# Pack_Supervisor_97x127mm_Rev_B.net
KiCad netlist of a schematic drawn in EAGLE
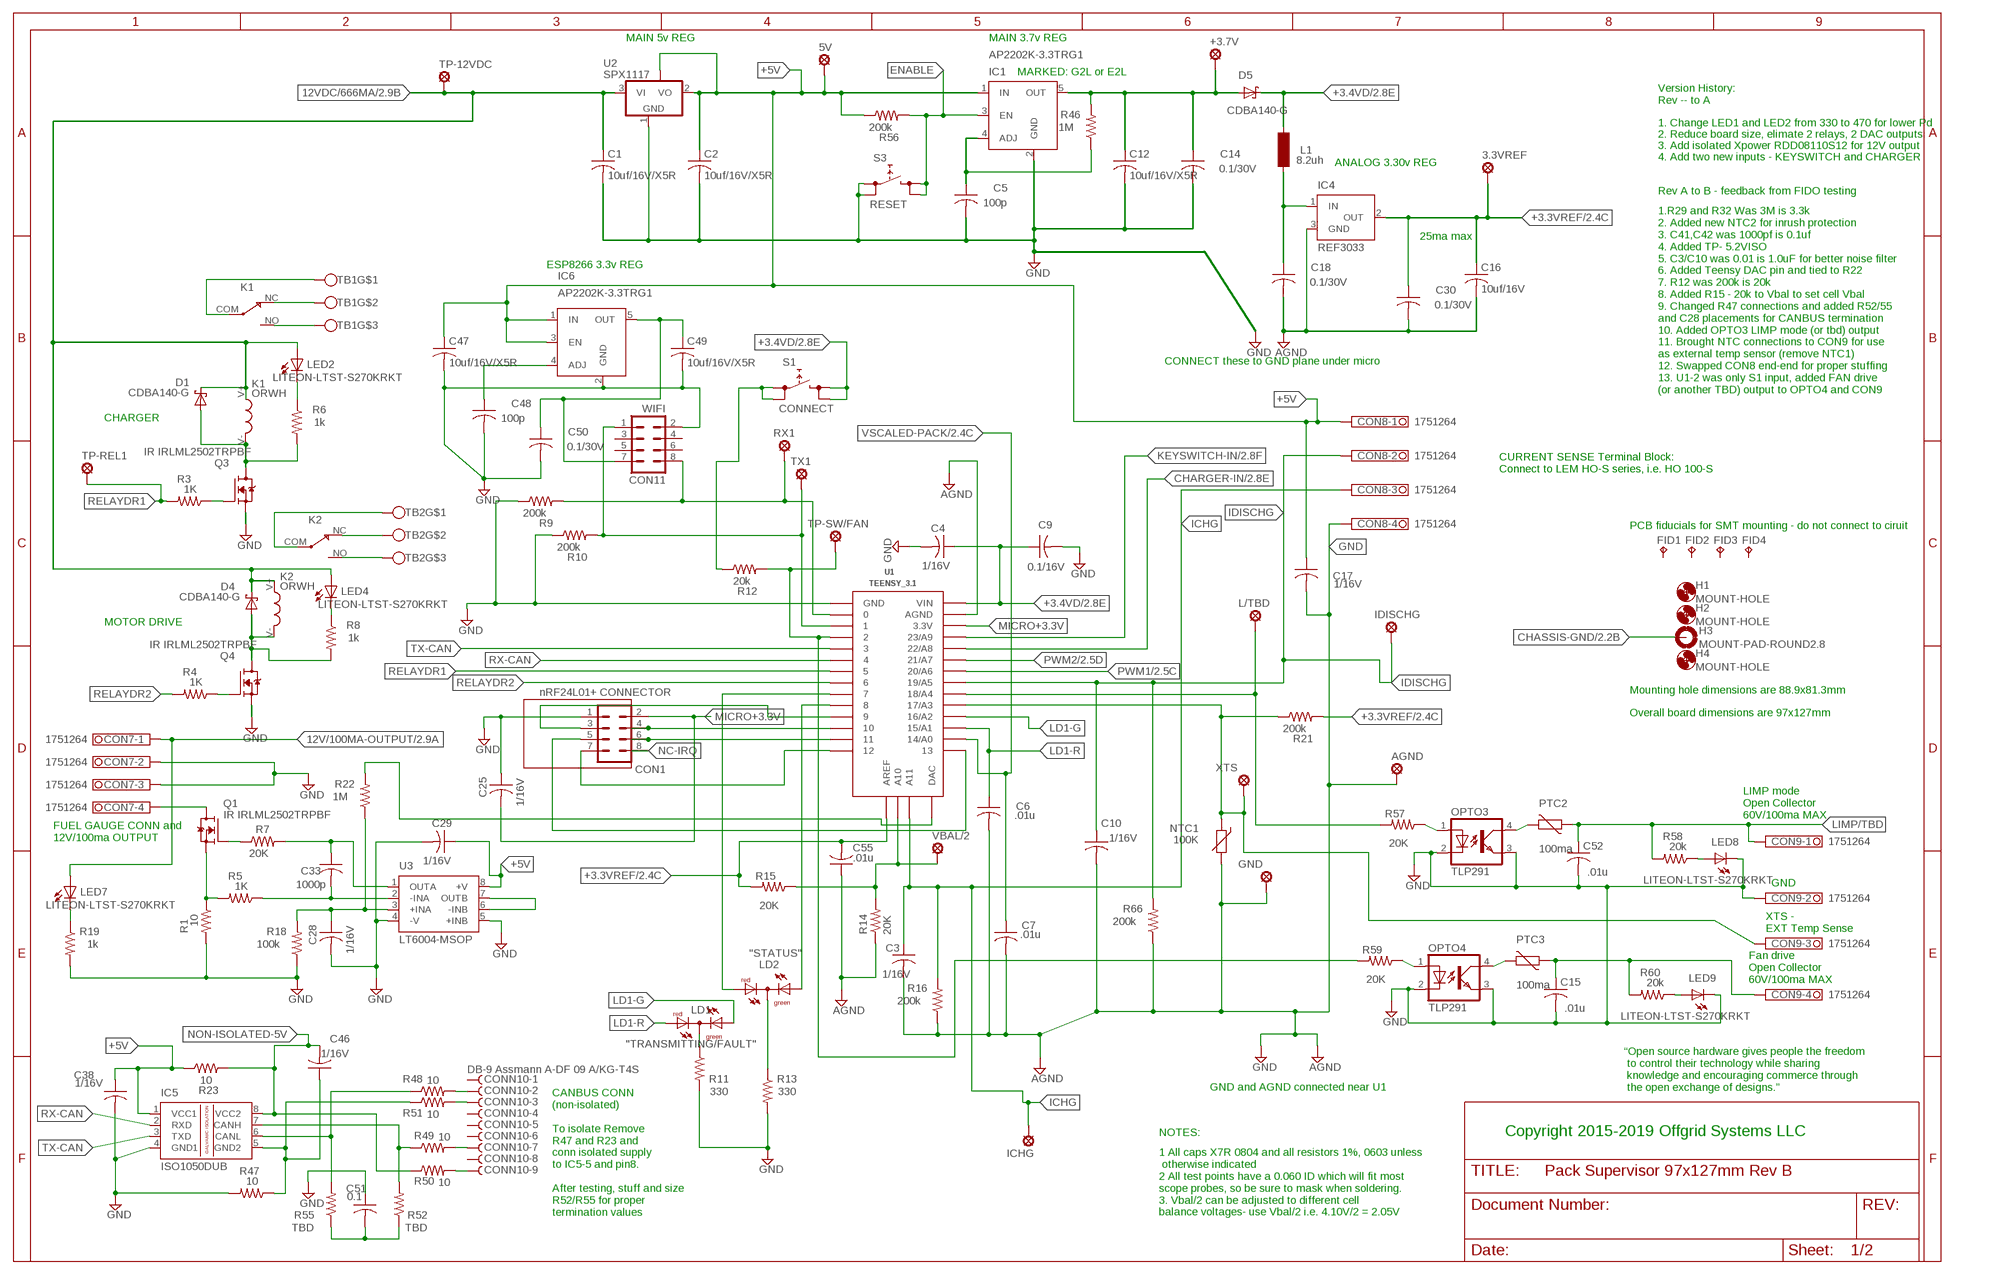
[diagram p0: schematic, sheet 1]
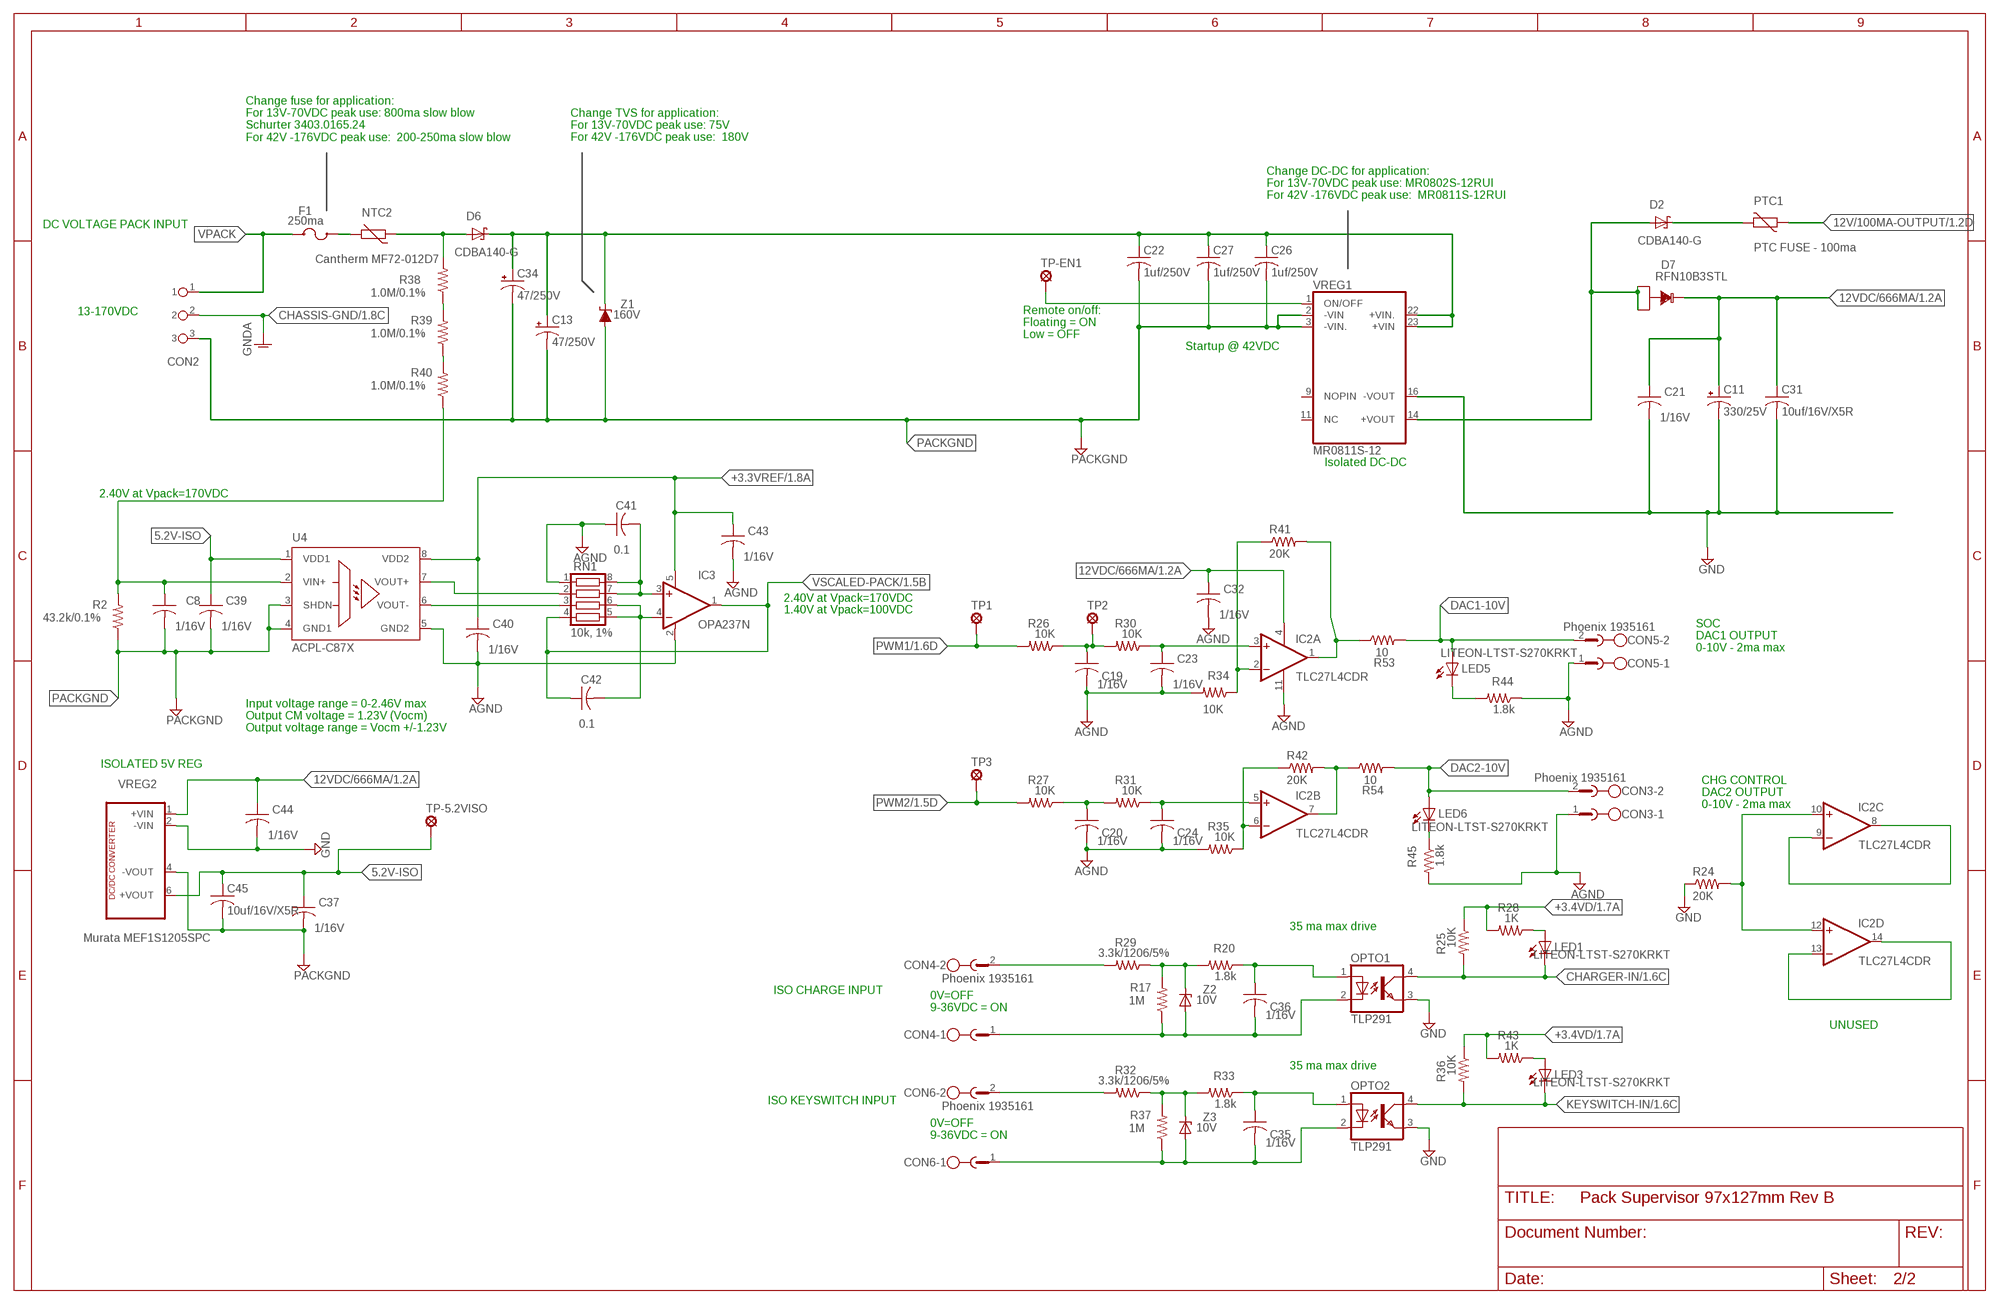
[diagram p1: schematic, sheet 2]

(export (version "E")
  (design (tool "Eeschema 10.0.6"))
  (components
    (comp (ref "+3.7V")
      (value "LSP10")
      (footprint "eagle-import:LSP10")
      (libsource (lib "eagle-import") (part "LSP10"))
    )
    (comp (ref "3.3VREF")
      (value "LSP10")
      (footprint "eagle-import:LSP10")
      (libsource (lib "eagle-import") (part "LSP10"))
    )
    (comp (ref "5V")
      (value "LSP10")
      (footprint "eagle-import:LSP10")
      (libsource (lib "eagle-import") (part "LSP10"))
    )
    (comp (ref "AGND")
      (value "LSP10")
      (footprint "eagle-import:LSP10")
      (libsource (lib "eagle-import") (part "LSP10"))
    )
    (comp (ref "C1")
      (value "10uf/16V/X5R")
      (footprint "eagle-import:C0805K")
      (fields (field (name "MPN") "Murata GRM21BR61C106ME15L"))
      (libsource (lib "eagle-import") (part "C-USC0805K"))
    )
    (comp (ref "C2")
      (value "10uf/16V/X5R")
      (footprint "eagle-import:C0805K")
      (fields (field (name "MPN") "Murata GRM21BR61C106ME15L"))
      (libsource (lib "eagle-import") (part "C-USC0805K"))
    )
    (comp (ref "C3")
      (value "1/16V")
      (footprint "eagle-import:TIMS_INDUCTOR_C0805")
      (fields (field (name "MPN") "Kemet C0805C103K5RACTU"))
      (libsource (lib "eagle-import") (part "TIMS_INDUCTOR_C-USC0805"))
    )
    (comp (ref "C4")
      (value "1/16V")
      (footprint "eagle-import:TIMS_INDUCTOR_C0805")
      (fields (field (name "MPN") "Kemet C0805C105K4RACTU"))
      (libsource (lib "eagle-import") (part "TIMS_INDUCTOR_C-USC0805"))
    )
    (comp (ref "C5")
      (value "100p")
      (footprint "eagle-import:TIMS_INDUCTOR_C0805")
      (fields (field (name "MPN") "Kemet C0805C104K5RACTU"))
      (libsource (lib "eagle-import") (part "TIMS_INDUCTOR_C-USC0805"))
    )
    (comp (ref "C6")
      (value ".01u")
      (footprint "eagle-import:TIMS_INDUCTOR_C0805")
      (fields (field (name "MPN") "Kemet C0805C103K5RACTU"))
      (libsource (lib "eagle-import") (part "TIMS_INDUCTOR_C-USC0805"))
    )
    (comp (ref "C7")
      (value ".01u")
      (footprint "eagle-import:TIMS_INDUCTOR_C0805")
      (fields (field (name "MPN") "Kemet C0805C103K5RACTU"))
      (libsource (lib "eagle-import") (part "TIMS_INDUCTOR_C-USC0805"))
    )
    (comp (ref "C9")
      (value "0.1/16V")
      (footprint "eagle-import:TIMS_INDUCTOR_C0805")
      (fields (field (name "MPN") "Kemet C0805C104K5RACTU"))
      (libsource (lib "eagle-import") (part "TIMS_INDUCTOR_C-USC0805"))
    )
    (comp (ref "C10")
      (value "1/16V")
      (footprint "eagle-import:TIMS_INDUCTOR_C0805")
      (fields (field (name "MPN") "Kemet C0805C103K5RACTU"))
      (libsource (lib "eagle-import") (part "TIMS_INDUCTOR_C-USC0805"))
    )
    (comp (ref "C12")
      (value "10uf/16V/X5R")
      (footprint "eagle-import:C0805K")
      (fields (field (name "MPN") "Murata GRM21BR61C106ME15L"))
      (libsource (lib "eagle-import") (part "C-USC0805K"))
    )
    (comp (ref "C14")
      (value "0.1/30V")
      (footprint "eagle-import:TIMS_INDUCTOR_C0805")
      (fields (field (name "MPN") "Kemet C0805C104K5RACTU"))
      (libsource (lib "eagle-import") (part "TIMS_INDUCTOR_C-USC0805"))
    )
    (comp (ref "C15")
      (value ".01u")
      (footprint "eagle-import:TIMS_INDUCTOR_C0805")
      (fields (field (name "MPN") "Kemet C0805C103K5RACTU"))
      (libsource (lib "eagle-import") (part "TIMS_INDUCTOR_C-USC0805"))
    )
    (comp (ref "C16")
      (value "10uf/16V")
      (footprint "eagle-import:C0805K")
      (fields (field (name "MPN") "Murata GRM21BR61A476ME15L"))
      (libsource (lib "eagle-import") (part "C-USC0805K"))
    )
    (comp (ref "C17")
      (value "1/16V")
      (footprint "eagle-import:TIMS_INDUCTOR_C0805")
      (fields (field (name "MPN") "Kemet C0805C105K4RACTU"))
      (libsource (lib "eagle-import") (part "TIMS_INDUCTOR_C-USC0805"))
    )
    (comp (ref "C18")
      (value "0.1/30V")
      (footprint "eagle-import:TIMS_INDUCTOR_C0805")
      (fields (field (name "MPN") "Kemet C0805C104K5RACTU"))
      (libsource (lib "eagle-import") (part "TIMS_INDUCTOR_C-USC0805"))
    )
    (comp (ref "C25")
      (value "1/16V")
      (footprint "eagle-import:TIMS_INDUCTOR_C0805")
      (fields (field (name "MPN") "Kemet C0805C105K4RACTU"))
      (libsource (lib "eagle-import") (part "TIMS_INDUCTOR_C-USC0805"))
    )
    (comp (ref "C28")
      (value "1/16V")
      (footprint "eagle-import:TIMS_INDUCTOR_C0805")
      (fields (field (name "MPN") "Kemet C0805C105K4RACTU"))
      (libsource (lib "eagle-import") (part "TIMS_INDUCTOR_C-USC0805"))
    )
    (comp (ref "C29")
      (value "1/16V")
      (footprint "eagle-import:TIMS_INDUCTOR_C0805")
      (fields (field (name "MPN") "Kemet C0805C105K4RACTU"))
      (libsource (lib "eagle-import") (part "TIMS_INDUCTOR_C-USC0805"))
    )
    (comp (ref "C30")
      (value "0.1/30V")
      (footprint "eagle-import:TIMS_INDUCTOR_C0805")
      (fields (field (name "MPN") "Kemet C0805C104K5RACTU"))
      (libsource (lib "eagle-import") (part "TIMS_INDUCTOR_C-USC0805"))
    )
    (comp (ref "C33")
      (value "1000p")
      (footprint "eagle-import:TIMS_INDUCTOR_C0805")
      (fields (field (name "MPN") "Kemet C0805C105K4RACTU"))
      (libsource (lib "eagle-import") (part "TIMS_INDUCTOR_C-USC0805"))
    )
    (comp (ref "C38")
      (value "1/16V")
      (footprint "eagle-import:TIMS_INDUCTOR_C0805")
      (fields (field (name "MPN") "Kemet C0805C105K4RACTU"))
      (libsource (lib "eagle-import") (part "TIMS_INDUCTOR_C-USC0805"))
    )
    (comp (ref "C46")
      (value "1/16V")
      (footprint "eagle-import:TIMS_INDUCTOR_C0805")
      (fields (field (name "MPN") "Kemet C0805C105K4RACTU"))
      (libsource (lib "eagle-import") (part "TIMS_INDUCTOR_C-USC0805"))
    )
    (comp (ref "C47")
      (value "10uf/16V/X5R")
      (footprint "eagle-import:C0805K")
      (fields (field (name "MPN") "Murata GRM21BR61C106ME15L"))
      (libsource (lib "eagle-import") (part "C-USC0805K"))
    )
    (comp (ref "C48")
      (value "100p")
      (footprint "eagle-import:TIMS_INDUCTOR_C0805")
      (fields (field (name "MPN") "Kemet C0805C104K5RACTU"))
      (libsource (lib "eagle-import") (part "TIMS_INDUCTOR_C-USC0805"))
    )
    (comp (ref "C49")
      (value "10uf/16V/X5R")
      (footprint "eagle-import:C0805K")
      (fields (field (name "MPN") "Murata GRM21BR61C106ME15L"))
      (libsource (lib "eagle-import") (part "C-USC0805K"))
    )
    (comp (ref "C50")
      (value "0.1/30V")
      (footprint "eagle-import:TIMS_INDUCTOR_C0805")
      (fields (field (name "MPN") "Kemet C0805C104K5RACTU"))
      (libsource (lib "eagle-import") (part "TIMS_INDUCTOR_C-USC0805"))
    )
    (comp (ref "C51")
      (value "0.1")
      (footprint "eagle-import:TIMS_INDUCTOR_C0805")
      (fields (field (name "MPN") "Kemet C0805C105K4RACTU"))
      (libsource (lib "eagle-import") (part "TIMS_INDUCTOR_C-USC0805"))
    )
    (comp (ref "C52")
      (value ".01u")
      (footprint "eagle-import:TIMS_INDUCTOR_C0805")
      (fields (field (name "MPN") "Kemet C0805C103K5RACTU"))
      (libsource (lib "eagle-import") (part "TIMS_INDUCTOR_C-USC0805"))
    )
    (comp (ref "C55")
      (value ".01u")
      (footprint "eagle-import:C0805")
      (fields (field (name "MPN") "Welwyn PCF0603R-3K01BT1"))
      (libsource (lib "eagle-import") (part "C-USC0805"))
    )
    (comp (ref "CON1")
      (value "nRF24L01+ CONNECTOR")
      (footprint "eagle-import:NRF24L01")
      (libsource (lib "eagle-import") (part "NRF24L01"))
    )
    (comp (ref "CON7")
      (value "1751264")
      (footprint "eagle-import:1751264")
      (libsource (lib "eagle-import") (part "1751264"))
    )
    (comp (ref "CON8")
      (value "1751264")
      (footprint "eagle-import:1751264")
      (libsource (lib "eagle-import") (part "1751264"))
    )
    (comp (ref "CON9")
      (value "1751264")
      (footprint "eagle-import:1751264")
      (libsource (lib "eagle-import") (part "1751264"))
    )
    (comp (ref "CON11")
      (value "WIFI")
      (footprint "eagle-import:MA04-2")
      (fields (field (name "MPN") "Sullins PPPC042LFBN-RC"))
      (libsource (lib "eagle-import") (part "MA04-2"))
    )
    (comp (ref "CONN10")
      (value "DB-9 Assmann A-DF 09 A/KG-T4S")
      (footprint "eagle-import:H5M09RA")
      (fields
        (field (name "100PCPRICE") ".563")
        (field (name "10PCPRICE") ".735")
        (field (name "MPN") "ASSMANN A-DS 09 A/KG-T4S")
      )
      (libsource (lib "eagle-import") (part "D-SUB9-H5M09RA"))
    )
    (comp (ref "D1")
      (value "CDBA140-G")
      (footprint "eagle-import:DO214AC")
      (fields (field (name "MPN") "comchip CDBA140-G"))
      (libsource (lib "eagle-import") (part "CDBA140-G"))
    )
    (comp (ref "D4")
      (value "CDBA140-G")
      (footprint "eagle-import:DO214AC")
      (fields (field (name "MPN") "comchip CDBA140-G"))
      (libsource (lib "eagle-import") (part "CDBA140-G"))
    )
    (comp (ref "D5")
      (value "CDBA140-G")
      (footprint "eagle-import:DO214AC")
      (fields (field (name "MPN") "comchip CDBA140-G"))
      (libsource (lib "eagle-import") (part "CDBA140-G"))
    )
    (comp (ref "FID1")
      (value "FIDUCIALTP10R")
      (footprint "eagle-import:TP10R")
      (libsource (lib "eagle-import") (part "FIDUCIALTP10R"))
    )
    (comp (ref "FID2")
      (value "FIDUCIALTP10R")
      (footprint "eagle-import:TP10R")
      (libsource (lib "eagle-import") (part "FIDUCIALTP10R"))
    )
    (comp (ref "FID3")
      (value "FIDUCIALTP10R")
      (footprint "eagle-import:TP10R")
      (libsource (lib "eagle-import") (part "FIDUCIALTP10R"))
    )
    (comp (ref "FID4")
      (value "FIDUCIALTP10R")
      (footprint "eagle-import:TP10R")
      (libsource (lib "eagle-import") (part "FIDUCIALTP10R"))
    )
    (comp (ref "GND")
      (value "LSP10")
      (footprint "eagle-import:LSP10")
      (libsource (lib "eagle-import") (part "LSP10"))
    )
    (comp (ref "H1")
      (value "MOUNT-HOLE")
      (footprint "eagle-import:2,6")
      (fields (field (name "MPN") "Keystone 9056"))
      (libsource (lib "eagle-import") (part "MOUNT-HOLE"))
    )
    (comp (ref "H2")
      (value "MOUNT-HOLE")
      (footprint "eagle-import:2,6")
      (libsource (lib "eagle-import") (part "MOUNT-HOLE"))
    )
    (comp (ref "H3")
      (value "MOUNT-PAD-ROUND2.8")
      (footprint "eagle-import:2,8-PAD")
      (libsource (lib "eagle-import") (part "MOUNT-PAD-ROUND2.8"))
    )
    (comp (ref "H4")
      (value "MOUNT-HOLE")
      (footprint "eagle-import:2,6")
      (libsource (lib "eagle-import") (part "MOUNT-HOLE"))
    )
    (comp (ref "IC1")
      (value "AP2202K-3.3TRG1")
      (footprint "eagle-import:SOT23-5")
      (fields
        (field (name "MF") "ALTERA CORPORATION")
        (field (name "MPN") "MIC5219BM5 TR")
        (field (name "MF_1") "Diodes INc")
        (field (name "MPN_1") "Diodes AP2202K-3.3TRG1")
      )
      (libsource (lib "eagle-import") (part "MIC5205"))
    )
    (comp (ref "IC4")
      (value "REF3033")
      (footprint "eagle-import:SOT23")
      (fields
        (field (name "MF") "MAXIM")
        (field (name "MPN") "MAX6520EUR-T")
        (field (name "MPN_1") "TI REF3033AIDBZR")
      )
      (libsource (lib "eagle-import") (part "MAX6520"))
    )
    (comp (ref "IC5")
      (value "ISO1050DUB")
      (footprint "eagle-import:DUB-R-PDSO-G8")
      (fields (field (name "MPN") "ISO1050DUBR") (field (name "MPN_1") "TI ISO1050DUBR"))
      (libsource (lib "eagle-import") (part "ISO1050DUB"))
    )
    (comp (ref "IC6")
      (value "AP2202K-3.3TRG1")
      (footprint "eagle-import:SOT23-5")
      (fields
        (field (name "MF") "ALTERA CORPORATION")
        (field (name "MPN") "MIC5219BM5 TR")
        (field (name "MF_1") "Diodes INc")
        (field (name "MPN_1") "Diodes AP2202K-3.3TRG1")
      )
      (libsource (lib "eagle-import") (part "MIC5205"))
    )
    (comp (ref "ICHG")
      (value "LSP10")
      (footprint "eagle-import:LSP10")
      (libsource (lib "eagle-import") (part "LSP10"))
    )
    (comp (ref "IDISCHG")
      (value "LSP10")
      (footprint "eagle-import:LSP10")
      (libsource (lib "eagle-import") (part "LSP10"))
    )
    (comp (ref "K1")
      (value "ORWH")
      (footprint "eagle-import:ORWH")
      (fields
        (field (name "MPN") "TE 1461069-5")
        (field (name "100PCPRICE") ".653")
        (field (name "1KPRICE") ".604")
      )
      (libsource (lib "eagle-import") (part "ORWH"))
    )
    (comp (ref "K2")
      (value "ORWH")
      (footprint "eagle-import:ORWH")
      (fields
        (field (name "MPN") "TE 1461069-5")
        (field (name "100PCPRICE") ".653")
        (field (name "1KPRICE") ".604")
      )
      (libsource (lib "eagle-import") (part "ORWH"))
    )
    (comp (ref "L/TBD")
      (value "LSP10")
      (footprint "eagle-import:LSP10")
      (libsource (lib "eagle-import") (part "LSP10"))
    )
    (comp (ref "L1")
      (value "8.2uh")
      (footprint "eagle-import:SM-1206")
      (fields (field (name "MPN") "Abracon AIML-1206-8R2K-T"))
      (libsource (lib "eagle-import") (part "SM-1206"))
    )
    (comp (ref "LD1")
      (value "\"TRANSMITTING/FAULT\"")
      (footprint "eagle-import:DUOLED-C-5MM")
      (fields (field (name "MPN") "Kingbright WP59EGC"))
      (libsource (lib "eagle-import") (part "DUOLED-RG-C"))
    )
    (comp (ref "LD2")
      (value "\"STATUS\"")
      (footprint "eagle-import:DUOLED-C-5MM")
      (fields (field (name "MPN") "Kingbright WP59EGC"))
      (libsource (lib "eagle-import") (part "DUOLED-RG-C"))
    )
    (comp (ref "LED2")
      (value "LITEON-LTST-S270KRKT")
      (footprint "eagle-import:LITEON-LTST-S270KRKT")
      (fields (field (name "MPN") "LiteOn LTST-S270KSKT "))
      (libsource (lib "eagle-import") (part "LITEON-LTST-S270KRKT"))
    )
    (comp (ref "LED4")
      (value "LITEON-LTST-S270KRKT")
      (footprint "eagle-import:LITEON-LTST-S270KRKT")
      (fields (field (name "MPN") "LiteOn LTST-S270KSKT "))
      (libsource (lib "eagle-import") (part "LITEON-LTST-S270KRKT"))
    )
    (comp (ref "LED7")
      (value "LITEON-LTST-S270KRKT")
      (footprint "eagle-import:LITEON-LTST-S270KRKT")
      (fields (field (name "MPN") "LiteOn LTST-S270KSKT "))
      (libsource (lib "eagle-import") (part "LITEON-LTST-S270KRKT"))
    )
    (comp (ref "LED8")
      (value "LITEON-LTST-S270KRKT")
      (footprint "eagle-import:LITEON-LTST-S270KRKT")
      (fields (field (name "MPN") "LiteOn LTST-S270KSKT "))
      (libsource (lib "eagle-import") (part "LITEON-LTST-S270KRKT"))
    )
    (comp (ref "LED9")
      (value "LITEON-LTST-S270KRKT")
      (footprint "eagle-import:LITEON-LTST-S270KRKT")
      (fields (field (name "MPN") "LiteOn LTST-S270KSKT "))
      (libsource (lib "eagle-import") (part "LITEON-LTST-S270KRKT"))
    )
    (comp (ref "NTC1")
      (value "100K")
      (footprint "eagle-import:0603")
      (fields (field (name "MPN") "MURATA NCP18WF104J03RB"))
      (libsource (lib "eagle-import") (part "NTC-MURATA-NCP18WF104J03RB"))
    )
    (comp (ref "OPTO3")
      (value "TLP291")
      (footprint "eagle-import:MINI-FLAT-4")
      (libsource (lib "eagle-import") (part "TLP283"))
    )
    (comp (ref "OPTO4")
      (value "TLP291")
      (footprint "eagle-import:MINI-FLAT-4")
      (libsource (lib "eagle-import") (part "TLP283"))
    )
    (comp (ref "PTC2")
      (value "100ma")
      (footprint "eagle-import:CT_CN0603")
      (fields (field (name "MPN") "Bel Fuse 0ZCM0010FF2G"))
      (libsource (lib "eagle-import") (part "VARISTORCN0603"))
    )
    (comp (ref "PTC3")
      (value "100ma")
      (footprint "eagle-import:CT_CN0603")
      (fields (field (name "MPN") "Bel Fuse 0ZCM0010FF2G"))
      (libsource (lib "eagle-import") (part "VARISTORCN0603"))
    )
    (comp (ref "Q1")
      (value "IRLML2502TRPBF")
      (footprint "eagle-import:SOT23")
      (fields (field (name "MPN") "IR IRLML2502TRPBF"))
      (libsource (lib "eagle-import") (part "IRLML2060TRPBF"))
    )
    (comp (ref "Q3")
      (value "IRLML2502TRPBF")
      (footprint "eagle-import:SOT23")
      (fields (field (name "MPN") "IR IRLML2502TRPBF"))
      (libsource (lib "eagle-import") (part "IRLML2060TRPBF"))
    )
    (comp (ref "Q4")
      (value "IRLML2502TRPBF")
      (footprint "eagle-import:SOT23")
      (fields (field (name "MPN") "IR IRLML2502TRPBF"))
      (libsource (lib "eagle-import") (part "IRLML2060TRPBF"))
    )
    (comp (ref "R1")
      (value "10")
      (footprint "eagle-import:R0603")
      (fields (field (name "MPN") "Bourns CR0603-FX-10R0ELF"))
      (libsource (lib "eagle-import") (part "rcl_R-US_R0603"))
    )
    (comp (ref "R3")
      (value "1K")
      (footprint "eagle-import:R0603")
      (fields (field (name "MPN") "Bourns CR0603-FX-1001ELF"))
      (libsource (lib "eagle-import") (part "rcl_R-US_R0603"))
    )
    (comp (ref "R4")
      (value "1K")
      (footprint "eagle-import:R0603")
      (fields (field (name "MPN") "Bourns CR0603-FX-1001ELF"))
      (libsource (lib "eagle-import") (part "rcl_R-US_R0603"))
    )
    (comp (ref "R5")
      (value "1K")
      (footprint "eagle-import:R0603")
      (fields (field (name "MPN") "Bourns CR0603-FX-1001ELF"))
      (libsource (lib "eagle-import") (part "rcl_R-US_R0603"))
    )
    (comp (ref "R6")
      (value "1k")
      (footprint "eagle-import:R0603")
      (fields (field (name "MPN") "Bourns CR0603-FX-3300ELF"))
      (libsource (lib "eagle-import") (part "rcl_R-US_R0603"))
    )
    (comp (ref "R7")
      (value "20K")
      (footprint "eagle-import:R0603")
      (fields (field (name "MPN") "Bourns CR0603-FX-2002ELF"))
      (libsource (lib "eagle-import") (part "rcl_R-US_R0603"))
    )
    (comp (ref "R8")
      (value "1k")
      (footprint "eagle-import:R0603")
      (fields (field (name "MPN") "Bourns CR0603-FX-3300ELF"))
      (libsource (lib "eagle-import") (part "rcl_R-US_R0603"))
    )
    (comp (ref "R9")
      (value "200k")
      (footprint "eagle-import:R0603")
      (fields (field (name "MPN") "Bourns CR0603-FX-2003ELF"))
      (libsource (lib "eagle-import") (part "rcl_R-US_R0603"))
    )
    (comp (ref "R10")
      (value "200k")
      (footprint "eagle-import:R0603")
      (fields (field (name "MPN") "Bourns CR0603-FX-2003ELF"))
      (libsource (lib "eagle-import") (part "rcl_R-US_R0603"))
    )
    (comp (ref "R11")
      (value "330")
      (footprint "eagle-import:R0603")
      (fields (field (name "MPN") "Bourns CR0603-FX-3300ELF"))
      (libsource (lib "eagle-import") (part "rcl_R-US_R0603"))
    )
    (comp (ref "R12")
      (value "20k")
      (footprint "eagle-import:R0603")
      (fields (field (name "MPN") "Bourns CR0603-FX-2003ELF"))
      (libsource (lib "eagle-import") (part "rcl_R-US_R0603"))
    )
    (comp (ref "R13")
      (value "330")
      (footprint "eagle-import:R0603")
      (fields (field (name "MPN") "Bourns CR0603-FX-3300ELF"))
      (libsource (lib "eagle-import") (part "rcl_R-US_R0603"))
    )
    (comp (ref "R14")
      (value "20K")
      (footprint "eagle-import:R0603")
      (fields (field (name "MPN") "Bourns CR0603-FX-2002ELF"))
      (libsource (lib "eagle-import") (part "rcl_R-US_R0603"))
    )
    (comp (ref "R15")
      (value "20K")
      (footprint "eagle-import:R0603")
      (fields (field (name "MPN") "Bourns CR0603-FX-2002ELF"))
      (libsource (lib "eagle-import") (part "rcl_R-US_R0603"))
    )
    (comp (ref "R16")
      (value "200k")
      (footprint "eagle-import:R0603")
      (fields (field (name "MPN") "Bourns CR0603-FX-2003ELF"))
      (libsource (lib "eagle-import") (part "rcl_R-US_R0603"))
    )
    (comp (ref "R18")
      (value "100k")
      (footprint "eagle-import:R0603")
      (fields (field (name "MPN") "Bourns CR0603-FX-1003ELF"))
      (libsource (lib "eagle-import") (part "rcl_R-US_R0603"))
    )
    (comp (ref "R19")
      (value "1k")
      (footprint "eagle-import:R0603")
      (fields (field (name "MPN") "Bourns CR0603-FX-3300ELF"))
      (libsource (lib "eagle-import") (part "rcl_R-US_R0603"))
    )
    (comp (ref "R21")
      (value "200k")
      (footprint "eagle-import:R0603")
      (fields (field (name "MPN") "Bourns CR0603-FX-2003ELF"))
      (libsource (lib "eagle-import") (part "rcl_R-US_R0603"))
    )
    (comp (ref "R22")
      (value "1M")
      (footprint "eagle-import:R0603")
      (fields (field (name "MPN") "Bourns CR0603-FX-1004ELF "))
      (libsource (lib "eagle-import") (part "rcl_R-US_R0603"))
    )
    (comp (ref "R23")
      (value "10")
      (footprint "eagle-import:R0603")
      (fields (field (name "MPN") "Bourns CR0603-FX-10R0ELF"))
      (libsource (lib "eagle-import") (part "rcl_R-US_R0603"))
    )
    (comp (ref "R46")
      (value "1M")
      (footprint "eagle-import:R0603")
      (fields (field (name "MPN") "Bourns CR0603-FX-1004ELF "))
      (libsource (lib "eagle-import") (part "rcl_R-US_R0603"))
    )
    (comp (ref "R47")
      (value "10")
      (footprint "eagle-import:R0603")
      (fields (field (name "MPN") "Bourns CR0603-FX-10R0ELF"))
      (libsource (lib "eagle-import") (part "rcl_R-US_R0603"))
    )
    (comp (ref "R48")
      (value "10")
      (footprint "eagle-import:R0603")
      (fields (field (name "MPN") "Bourns CR0603-FX-10R0ELF"))
      (libsource (lib "eagle-import") (part "rcl_R-US_R0603"))
    )
    (comp (ref "R49")
      (value "10")
      (footprint "eagle-import:R0603")
      (fields (field (name "MPN") "Bourns CR0603-FX-10R0ELF"))
      (libsource (lib "eagle-import") (part "rcl_R-US_R0603"))
    )
    (comp (ref "R50")
      (value "10")
      (footprint "eagle-import:R0603")
      (fields (field (name "MPN") "Bourns CR0603-FX-10R0ELF"))
      (libsource (lib "eagle-import") (part "rcl_R-US_R0603"))
    )
    (comp (ref "R51")
      (value "10")
      (footprint "eagle-import:R0603")
      (fields (field (name "MPN") "Bourns CR0603-FX-10R0ELF"))
      (libsource (lib "eagle-import") (part "rcl_R-US_R0603"))
    )
    (comp (ref "R52")
      (value "TBD")
      (footprint "eagle-import:0207_5V")
      (libsource (lib "eagle-import") (part "R-US_0207/5V"))
    )
    (comp (ref "R55")
      (value "TBD")
      (footprint "eagle-import:0207_5V")
      (libsource (lib "eagle-import") (part "R-US_0207/5V"))
    )
    (comp (ref "R56")
      (value "200k")
      (footprint "eagle-import:R0603")
      (fields (field (name "MPN") "Bourns CR0603-FX-2003ELF"))
      (libsource (lib "eagle-import") (part "rcl_R-US_R0603"))
    )
    (comp (ref "R57")
      (value "20K")
      (footprint "eagle-import:R0603")
      (fields (field (name "MPN") "Bourns CR0603-FX-2002ELF"))
      (libsource (lib "eagle-import") (part "rcl_R-US_R0603"))
    )
    (comp (ref "R58")
      (value "20k")
      (footprint "eagle-import:R0603")
      (fields (field (name "MPN") "Bourns CR0603-FX-1001ELF"))
      (libsource (lib "eagle-import") (part "rcl_R-US_R0603"))
    )
    (comp (ref "R59")
      (value "20K")
      (footprint "eagle-import:R0603")
      (fields (field (name "MPN") "Bourns CR0603-FX-2002ELF"))
      (libsource (lib "eagle-import") (part "rcl_R-US_R0603"))
    )
    (comp (ref "R60")
      (value "20k")
      (footprint "eagle-import:R0603")
      (fields (field (name "MPN") "Bourns CR0603-FX-1001ELF"))
      (libsource (lib "eagle-import") (part "rcl_R-US_R0603"))
    )
    (comp (ref "R66")
      (value "200k")
      (footprint "eagle-import:R0603")
      (fields (field (name "MPN") "Bourns CR0603-FX-2003ELF"))
      (libsource (lib "eagle-import") (part "rcl_R-US_R0603"))
    )
    (comp (ref "RX1")
      (value "LSP10")
      (footprint "eagle-import:LSP10")
      (libsource (lib "eagle-import") (part "LSP10"))
    )
    (comp (ref "S1")
      (value "CONNECT")
      (footprint "eagle-import:PTS645")
      (fields (field (name "MPN") "C&k PTS645SM43SMTR92 LFS"))
      (libsource (lib "eagle-import") (part "PTS645"))
    )
    (comp (ref "S3")
      (value "RESET")
      (footprint "eagle-import:PTS645")
      (fields (field (name "MPN") "C&k PTS645SM43SMTR92 LFS"))
      (libsource (lib "eagle-import") (part "PTS645"))
    )
    (comp (ref "TB1")
      (value "TE-5-1437652-4")
      (footprint "eagle-import:TE-5-1437652-4")
      (fields
        (field (name "100PCPRICE") "1.16")
        (field (name "1KPRICE") ".84")
        (field (name "MPN") "TE 5-1437652-4")
      )
      (libsource (lib "eagle-import") (part "TE-5-1437652-4"))
    )
    (comp (ref "TB2")
      (value "TE-5-1437652-4")
      (footprint "eagle-import:TE-5-1437652-4")
      (fields
        (field (name "MPN") "TE 5-1437652-4")
        (field (name "100PCPRICE") "1.16")
        (field (name "1KPRICE") ".84")
      )
      (libsource (lib "eagle-import") (part "TE-5-1437652-4"))
    )
    (comp (ref "TP-12VDC")
      (value "LSP10")
      (footprint "eagle-import:LSP10")
      (libsource (lib "eagle-import") (part "LSP10"))
    )
    (comp (ref "TP-REL1")
      (value "LSP10")
      (footprint "eagle-import:LSP10")
      (libsource (lib "eagle-import") (part "LSP10"))
    )
    (comp (ref "TP-SW/FAN")
      (value "LSP10")
      (footprint "eagle-import:LSP10")
      (libsource (lib "eagle-import") (part "LSP10"))
    )
    (comp (ref "TX1")
      (value "LSP10")
      (footprint "eagle-import:LSP10")
      (libsource (lib "eagle-import") (part "LSP10"))
    )
    (comp (ref "U1")
      (value "TEENSY_3.1")
      (footprint "eagle-import:TEENSY_3.0-DIP+ANALOG+DAC")
      (fields (field (name "MPN") "OshPark Teensy 3.1"))
      (libsource (lib "eagle-import") (part "TEENSY_3.0-DIP+ANALOG"))
    )
    (comp (ref "U2")
      (value "SPX1117")
      (footprint "eagle-import:SOT223")
      (fields (field (name "MPN") "Exar SPX1117M3-L-5-0/TR"))
      (libsource (lib "eagle-import") (part "SPX1117"))
    )
    (comp (ref "U3")
      (value "LT6004-MSOP")
      (footprint "eagle-import:LT6004-MSOP")
      (fields (field (name "MPN") "LTC LT6004CMS8"))
      (libsource (lib "eagle-import") (part "LT6004-MSOP"))
    )
    (comp (ref "VBAL/2")
      (value "LSP10")
      (footprint "eagle-import:LSP10")
      (libsource (lib "eagle-import") (part "LSP10"))
    )
    (comp (ref "XTS")
      (value "LSP10")
      (footprint "eagle-import:LSP10")
      (libsource (lib "eagle-import") (part "LSP10"))
    )
    (comp (ref "C8")
      (value "1/16V")
      (footprint "eagle-import:TIMS_INDUCTOR_C0805")
      (fields (field (name "MPN") "Kemet C0805C105K4RACTU"))
      (libsource (lib "eagle-import") (part "TIMS_INDUCTOR_C-USC0805"))
    )
    (comp (ref "C11")
      (value "330/25V")
      (footprint "eagle-import:E5-10,5")
      (libsource (lib "eagle-import") (part "CPOL-USE5-10.5"))
    )
    (comp (ref "C13")
      (value "47/250V")
      (footprint "eagle-import:E5-13")
      (fields (field (name "MPN") "PANASONIC ECA-2EM470"))
      (libsource (lib "eagle-import") (part "CPOL-USE5-13"))
    )
    (comp (ref "C19")
      (value "1/16V")
      (footprint "eagle-import:TIMS_INDUCTOR_C0805")
      (fields (field (name "MPN") "Kemet C0805C105K4RACTU"))
      (libsource (lib "eagle-import") (part "TIMS_INDUCTOR_C-USC0805"))
    )
    (comp (ref "C20")
      (value "1/16V")
      (footprint "eagle-import:TIMS_INDUCTOR_C0805")
      (fields (field (name "MPN") "Kemet C0805C105K4RACTU"))
      (libsource (lib "eagle-import") (part "TIMS_INDUCTOR_C-USC0805"))
    )
    (comp (ref "C21")
      (value "1/16V")
      (footprint "eagle-import:TIMS_INDUCTOR_C0805")
      (fields (field (name "MPN") "Kemet C0805C105K4RACTU"))
      (libsource (lib "eagle-import") (part "TIMS_INDUCTOR_C-USC0805"))
    )
    (comp (ref "C22")
      (value "1uf/250V")
      (footprint "eagle-import:RCL_C050-030X075")
      (libsource (lib "eagle-import") (part "RCL_C-US050-030X075"))
    )
    (comp (ref "C23")
      (value "1/16V")
      (footprint "eagle-import:TIMS_INDUCTOR_C0805")
      (fields (field (name "MPN") "Kemet C0805C105K4RACTU"))
      (libsource (lib "eagle-import") (part "TIMS_INDUCTOR_C-USC0805"))
    )
    (comp (ref "C24")
      (value "1/16V")
      (footprint "eagle-import:TIMS_INDUCTOR_C0805")
      (fields (field (name "MPN") "Kemet C0805C105K4RACTU"))
      (libsource (lib "eagle-import") (part "TIMS_INDUCTOR_C-USC0805"))
    )
    (comp (ref "C26")
      (value "1uf/250V")
      (footprint "eagle-import:RCL_C050-030X075")
      (libsource (lib "eagle-import") (part "RCL_C-US050-030X075"))
    )
    (comp (ref "C27")
      (value "1uf/250V")
      (footprint "eagle-import:RCL_C050-030X075")
      (libsource (lib "eagle-import") (part "RCL_C-US050-030X075"))
    )
    (comp (ref "C31")
      (value "10uf/16V/X5R")
      (footprint "eagle-import:C0805K")
      (fields (field (name "MPN") "Murata GRM21BR61C106ME15L"))
      (libsource (lib "eagle-import") (part "C-USC0805K"))
    )
    (comp (ref "C32")
      (value "1/16V")
      (footprint "eagle-import:TIMS_INDUCTOR_C0805")
      (fields (field (name "MPN") "Kemet C0805C105K4RACTU"))
      (libsource (lib "eagle-import") (part "TIMS_INDUCTOR_C-USC0805"))
    )
    (comp (ref "C34")
      (value "47/250V")
      (footprint "eagle-import:E5-13")
      (fields (field (name "MPN") "PANASONIC ECA-2EM470"))
      (libsource (lib "eagle-import") (part "CPOL-USE5-13"))
    )
    (comp (ref "C35")
      (value "1/16V")
      (footprint "eagle-import:TIMS_INDUCTOR_C0805")
      (fields (field (name "MPN") "Kemet C0805C105K4RACTU"))
      (libsource (lib "eagle-import") (part "TIMS_INDUCTOR_C-USC0805"))
    )
    (comp (ref "C36")
      (value "1/16V")
      (footprint "eagle-import:TIMS_INDUCTOR_C0805")
      (fields (field (name "MPN") "Kemet C0805C105K4RACTU"))
      (libsource (lib "eagle-import") (part "TIMS_INDUCTOR_C-USC0805"))
    )
    (comp (ref "C37")
      (value "1/16V")
      (footprint "eagle-import:TIMS_INDUCTOR_C0805")
      (fields (field (name "MPN") "Kemet C0805C105K4RACTU"))
      (libsource (lib "eagle-import") (part "TIMS_INDUCTOR_C-USC0805"))
    )
    (comp (ref "C39")
      (value "1/16V")
      (footprint "eagle-import:TIMS_INDUCTOR_C0805")
      (fields (field (name "MPN") "Kemet C0805C105K4RACTU"))
      (libsource (lib "eagle-import") (part "TIMS_INDUCTOR_C-USC0805"))
    )
    (comp (ref "C40")
      (value "1/16V")
      (footprint "eagle-import:TIMS_INDUCTOR_C0805")
      (fields (field (name "MPN") "Kemet C0805C105K4RACTU"))
      (libsource (lib "eagle-import") (part "TIMS_INDUCTOR_C-USC0805"))
    )
    (comp (ref "C41")
      (value "0.1")
      (footprint "eagle-import:TIMS_INDUCTOR_C0805")
      (fields (field (name "MPN") "Kemet C0805C105K4RACTU"))
      (libsource (lib "eagle-import") (part "TIMS_INDUCTOR_C-USC0805"))
    )
    (comp (ref "C42")
      (value "0.1")
      (footprint "eagle-import:TIMS_INDUCTOR_C0805")
      (fields (field (name "MPN") "Kemet C0805C105K4RACTU"))
      (libsource (lib "eagle-import") (part "TIMS_INDUCTOR_C-USC0805"))
    )
    (comp (ref "C43")
      (value "1/16V")
      (footprint "eagle-import:TIMS_INDUCTOR_C0805")
      (fields (field (name "MPN") "Kemet C0805C105K4RACTU"))
      (libsource (lib "eagle-import") (part "TIMS_INDUCTOR_C-USC0805"))
    )
    (comp (ref "C44")
      (value "1/16V")
      (footprint "eagle-import:TIMS_INDUCTOR_C0805")
      (fields (field (name "MPN") "Kemet C0805C105K4RACTU"))
      (libsource (lib "eagle-import") (part "TIMS_INDUCTOR_C-USC0805"))
    )
    (comp (ref "C45")
      (value "10uf/16V/X5R")
      (footprint "eagle-import:C0805K")
      (fields (field (name "MPN") "Murata GRM21BR61C106ME15L"))
      (libsource (lib "eagle-import") (part "C-USC0805K"))
    )
    (comp (ref "CON2")
      (value "TYCO-796739-3")
      (footprint "eagle-import:TYCO-796739-3")
      (libsource (lib "eagle-import") (part "TYCO-796739-3"))
    )
    (comp (ref "CON3")
      (value "Phoenix 1935161")
      (footprint "eagle-import:MSTBV2")
      (fields
        (field (name "MPN") "Phoenix 1935161")
        (field (name "100PCPRICE") ".327")
        (field (name "10PCPRICE") ".352")
      )
      (libsource (lib "eagle-import") (part "MSTBV2"))
    )
    (comp (ref "CON4")
      (value "Phoenix 1935161")
      (footprint "eagle-import:MSTBV2")
      (fields
        (field (name "MPN") "Phoenix 1935161")
        (field (name "100PCPRICE") ".327")
        (field (name "10PCPRICE") ".352")
      )
      (libsource (lib "eagle-import") (part "MSTBV2"))
    )
    (comp (ref "CON5")
      (value "Phoenix 1935161")
      (footprint "eagle-import:MSTBV2")
      (fields
        (field (name "100PCPRICE") ".327")
        (field (name "10PCPRICE") ".352")
        (field (name "MPN") "Phoenix 1935161")
      )
      (libsource (lib "eagle-import") (part "MSTBV2"))
    )
    (comp (ref "CON6")
      (value "Phoenix 1935161")
      (footprint "eagle-import:MSTBV2")
      (fields
        (field (name "100PCPRICE") ".327")
        (field (name "10PCPRICE") ".352")
        (field (name "MPN") "Phoenix 1935161")
      )
      (libsource (lib "eagle-import") (part "MSTBV2"))
    )
    (comp (ref "D2")
      (value "CDBA140-G")
      (footprint "eagle-import:DO214AC")
      (fields (field (name "MPN") "comchip CDBA140-G"))
      (libsource (lib "eagle-import") (part "CDBA140-G"))
    )
    (comp (ref "D6")
      (value "CDBA140-G")
      (footprint "eagle-import:DO214AC")
      (fields (field (name "MPN") "comchip CDBA140-G"))
      (libsource (lib "eagle-import") (part "CDBA140-G"))
    )
    (comp (ref "D7")
      (value "RFN10B3STL")
      (footprint "eagle-import:TO252-FATPADS")
      (fields (field (name "MPN") "ROHM RFN10B3STL"))
      (libsource (lib "eagle-import") (part "RFN10B3STL"))
    )
    (comp (ref "F1")
      (value "250ma")
      (footprint "eagle-import:SCHURTER-UMT250")
      (fields (field (name "MPN") "Schurter 3403.0159.24"))
      (libsource (lib "eagle-import") (part "SCHURTER-UMT250"))
    )
    (comp (ref "IC2")
      (value "TLC27L4CDR")
      (footprint "eagle-import:SO14")
      (fields
        (field (name "100PCPRICE") ".581")
        (field (name "1KPRICE") ".39")
        (field (name "MPN") "TI TLC27L4CDR")
      )
      (libsource (lib "eagle-import") (part "OPA4UA134"))
    )
    (comp (ref "IC3")
      (value "OPA237N")
      (footprint "eagle-import:SOT23-5")
      (fields (field (name "MPN") "TI OPA237NA/3K"))
      (libsource (lib "eagle-import") (part "OPA237N"))
    )
    (comp (ref "LED1")
      (value "LITEON-LTST-S270KRKT")
      (footprint "eagle-import:LITEON-LTST-S270KRKT")
      (fields (field (name "MPN") "LiteOn LTST-S270KSKT "))
      (libsource (lib "eagle-import") (part "LITEON-LTST-S270KRKT"))
    )
    (comp (ref "LED3")
      (value "LITEON-LTST-S270KRKT")
      (footprint "eagle-import:LITEON-LTST-S270KRKT")
      (fields (field (name "MPN") "LiteOn LTST-S270KSKT "))
      (libsource (lib "eagle-import") (part "LITEON-LTST-S270KRKT"))
    )
    (comp (ref "LED5")
      (value "LITEON-LTST-S270KRKT")
      (footprint "eagle-import:LITEON-LTST-S270KRKT")
      (fields (field (name "MPN") "LiteOn LTST-S270KSKT "))
      (libsource (lib "eagle-import") (part "LITEON-LTST-S270KRKT"))
    )
    (comp (ref "LED6")
      (value "LITEON-LTST-S270KRKT")
      (footprint "eagle-import:LITEON-LTST-S270KRKT")
      (fields (field (name "MPN") "LiteOn LTST-S270KSKT "))
      (libsource (lib "eagle-import") (part "LITEON-LTST-S270KRKT"))
    )
    (comp (ref "NTC2")
      (value "Cantherm MF72-012D7")
      (footprint "eagle-import:D7-PACKAGE")
      (libsource (lib "eagle-import") (part "NTC-GLASS"))
    )
    (comp (ref "OPTO1")
      (value "TLP291")
      (footprint "eagle-import:MINI-FLAT-4")
      (libsource (lib "eagle-import") (part "TLP283"))
    )
    (comp (ref "OPTO2")
      (value "TLP291")
      (footprint "eagle-import:MINI-FLAT-4")
      (libsource (lib "eagle-import") (part "TLP283"))
    )
    (comp (ref "PTC1")
      (value "PTC FUSE - 100ma")
      (footprint "eagle-import:CT_CN0603")
      (fields (field (name "MPN") "Bel Fuse 0ZCM0010FF2G"))
      (libsource (lib "eagle-import") (part "VARISTORCN0603"))
    )
    (comp (ref "R2")
      (value "43.2k/0.1%")
      (footprint "eagle-import:R0603")
      (fields (field (name "MPN") "Panasonic ERA-3AEB4322V "))
      (libsource (lib "eagle-import") (part "rcl_R-US_R0603"))
    )
    (comp (ref "R17")
      (value "1M")
      (footprint "eagle-import:R0603")
      (fields (field (name "MPN") "Bourns CR0603-FX-1004ELF "))
      (libsource (lib "eagle-import") (part "rcl_R-US_R0603"))
    )
    (comp (ref "R20")
      (value "1.8k")
      (footprint "eagle-import:R0603")
      (fields (field (name "MPN") "Bourns CR0603-FX-1821ELF"))
      (libsource (lib "eagle-import") (part "rcl_R-US_R0603"))
    )
    (comp (ref "R24")
      (value "20K")
      (footprint "eagle-import:R0603")
      (fields (field (name "MPN") "Bourns CR0603-FX-2002ELF"))
      (libsource (lib "eagle-import") (part "rcl_R-US_R0603"))
    )
    (comp (ref "R25")
      (value "10K")
      (footprint "eagle-import:R0603")
      (fields (field (name "MPN") "Bourns CR0603-FX-1002ELF"))
      (libsource (lib "eagle-import") (part "rcl_R-US_R0603"))
    )
    (comp (ref "R26")
      (value "10K")
      (footprint "eagle-import:R0603")
      (fields (field (name "MPN") "Bourns CR0603-FX-1002ELF"))
      (libsource (lib "eagle-import") (part "rcl_R-US_R0603"))
    )
    (comp (ref "R27")
      (value "10K")
      (footprint "eagle-import:R0603")
      (fields (field (name "MPN") "Bourns CR0603-FX-1002ELF"))
      (libsource (lib "eagle-import") (part "rcl_R-US_R0603"))
    )
    (comp (ref "R28")
      (value "1K")
      (footprint "eagle-import:R0603")
      (fields (field (name "MPN") "Bourns CR0603-FX-1001ELF"))
      (libsource (lib "eagle-import") (part "rcl_R-US_R0603"))
    )
    (comp (ref "R29")
      (value "3.3k/1206/5%")
      (footprint "eagle-import:R1206")
      (fields (field (name "MPN") "Panasonic ERJ-8GEYJ305V"))
      (libsource (lib "eagle-import") (part "rcl_R-US_R1206"))
    )
    (comp (ref "R30")
      (value "10K")
      (footprint "eagle-import:R0603")
      (fields (field (name "MPN") "Bourns CR0603-FX-1002ELF"))
      (libsource (lib "eagle-import") (part "rcl_R-US_R0603"))
    )
    (comp (ref "R31")
      (value "10K")
      (footprint "eagle-import:R0603")
      (fields (field (name "MPN") "Bourns CR0603-FX-1002ELF"))
      (libsource (lib "eagle-import") (part "rcl_R-US_R0603"))
    )
    (comp (ref "R32")
      (value "3.3k/1206/5%")
      (footprint "eagle-import:R1206")
      (fields (field (name "MPN") "Panasonic ERJ-8GEYJ305V"))
      (libsource (lib "eagle-import") (part "rcl_R-US_R1206"))
    )
    (comp (ref "R33")
      (value "1.8k")
      (footprint "eagle-import:R0603")
      (fields (field (name "MPN") "Bourns CR0603-FX-1821ELF"))
      (libsource (lib "eagle-import") (part "rcl_R-US_R0603"))
    )
    (comp (ref "R34")
      (value "10K")
      (footprint "eagle-import:R0603")
      (fields (field (name "MPN") "Bourns CR0603-FX-1002ELF"))
      (libsource (lib "eagle-import") (part "rcl_R-US_R0603"))
    )
    (comp (ref "R35")
      (value "10K")
      (footprint "eagle-import:R0603")
      (fields (field (name "MPN") "Bourns CR0603-FX-1002ELF"))
      (libsource (lib "eagle-import") (part "rcl_R-US_R0603"))
    )
    (comp (ref "R36")
      (value "10K")
      (footprint "eagle-import:R0603")
      (fields (field (name "MPN") "Bourns CR0603-FX-1002ELF"))
      (libsource (lib "eagle-import") (part "rcl_R-US_R0603"))
    )
    (comp (ref "R37")
      (value "1M")
      (footprint "eagle-import:R0603")
      (fields (field (name "MPN") "Bourns CR0603-FX-1004ELF "))
      (libsource (lib "eagle-import") (part "rcl_R-US_R0603"))
    )
    (comp (ref "R38")
      (value "1.0M/0.1%")
      (footprint "eagle-import:R0805")
      (fields (field (name "MPN") "Panasonic ERA-6AEB105V"))
      (libsource (lib "eagle-import") (part "rcl_R-US_R0805"))
    )
    (comp (ref "R39")
      (value "1.0M/0.1%")
      (footprint "eagle-import:R0805")
      (fields (field (name "MPN") "Panasonic ERA-6AEB105V"))
      (libsource (lib "eagle-import") (part "rcl_R-US_R0805"))
    )
    (comp (ref "R40")
      (value "1.0M/0.1%")
      (footprint "eagle-import:R0805")
      (fields (field (name "MPN") "Panasonic ERA-6AEB105V"))
      (libsource (lib "eagle-import") (part "rcl_R-US_R0805"))
    )
    (comp (ref "R41")
      (value "20K")
      (footprint "eagle-import:R0603")
      (fields (field (name "MPN") "Bourns CR0603-FX-2002ELF"))
      (libsource (lib "eagle-import") (part "rcl_R-US_R0603"))
    )
    (comp (ref "R42")
      (value "20K")
      (footprint "eagle-import:R0603")
      (fields (field (name "MPN") "Bourns CR0603-FX-2002ELF"))
      (libsource (lib "eagle-import") (part "rcl_R-US_R0603"))
    )
    (comp (ref "R43")
      (value "1K")
      (footprint "eagle-import:R0603")
      (fields (field (name "MPN") "Bourns CR0603-FX-1001ELF"))
      (libsource (lib "eagle-import") (part "rcl_R-US_R0603"))
    )
    (comp (ref "R44")
      (value "1.8k")
      (footprint "eagle-import:R0603")
      (fields (field (name "MPN") "Bourns CR0603-FX-1821ELF"))
      (libsource (lib "eagle-import") (part "rcl_R-US_R0603"))
    )
    (comp (ref "R45")
      (value "1.8k")
      (footprint "eagle-import:R0603")
      (fields (field (name "MPN") "Bourns CR0603-FX-1821ELF"))
      (libsource (lib "eagle-import") (part "rcl_R-US_R0603"))
    )
    (comp (ref "R53")
      (value "10")
      (footprint "eagle-import:R0603")
      (fields (field (name "MPN") "Bourns CR0603-FX-10R0ELF"))
      (libsource (lib "eagle-import") (part "rcl_R-US_R0603"))
    )
    (comp (ref "R54")
      (value "10")
      (footprint "eagle-import:R0603")
      (fields (field (name "MPN") "Bourns CR0603-FX-10R0ELF"))
      (libsource (lib "eagle-import") (part "rcl_R-US_R0603"))
    )
    (comp (ref "RN1")
      (value "10k, 1%")
      (footprint "eagle-import:CTS742C083")
      (fields (field (name "MPN") "Yageo TC164-FR-0710KL"))
      (libsource (lib "eagle-import") (part "CTS742C083"))
    )
    (comp (ref "TP-5.2VISO")
      (value "LSP10")
      (footprint "eagle-import:LSP10")
      (libsource (lib "eagle-import") (part "LSP10"))
    )
    (comp (ref "TP-EN1")
      (value "LSP10")
      (footprint "eagle-import:LSP10")
      (libsource (lib "eagle-import") (part "LSP10"))
    )
    (comp (ref "TP1")
      (value "LSP10")
      (footprint "eagle-import:LSP10")
      (libsource (lib "eagle-import") (part "LSP10"))
    )
    (comp (ref "TP2")
      (value "LSP10")
      (footprint "eagle-import:LSP10")
      (libsource (lib "eagle-import") (part "LSP10"))
    )
    (comp (ref "TP3")
      (value "LSP10")
      (footprint "eagle-import:LSP10")
      (libsource (lib "eagle-import") (part "LSP10"))
    )
    (comp (ref "U4")
      (value "ACPL-C87X")
      (footprint "eagle-import:STRETCH-SO8")
      (fields (field (name "MPN") "Avago Broadcomm ACPL-C87B-000E"))
      (libsource (lib "eagle-import") (part "ACPL-C87X"))
    )
    (comp (ref "VREG1")
      (value "MR0811S-12")
      (footprint "eagle-import:MR0811S-12")
      (fields (field (name "MPN") "Micropower Direct MR0811S-12RUI"))
      (libsource (lib "eagle-import") (part "MR0811S-12"))
    )
    (comp (ref "VREG2")
      (value "Murata MEF1S1205SPC")
      (footprint "eagle-import:MURATA-MEF")
      (libsource (lib "eagle-import") (part "MURATA-MEF-ISODCDC"))
    )
    (comp (ref "Z1")
      (value "160V")
      (footprint "eagle-import:SMB")
      (fields (field (name "MPN") "ON SEMI 1SMB5954BT3G"))
      (libsource (lib "eagle-import") (part "ZENER-SMB"))
    )
    (comp (ref "Z2")
      (value "10V")
      (footprint "eagle-import:TIMS_DIODE_SOT23")
      (fields (field (name "MPN") "ON SEMI SZBZX84C10LT1G"))
      (libsource (lib "eagle-import") (part "TIMS_DIODE_ZENER-DIODESOT23"))
    )
    (comp (ref "Z3")
      (value "10V")
      (footprint "eagle-import:TIMS_DIODE_SOT23")
      (fields (field (name "MPN") "ON SEMI SZBZX84C10LT1G"))
      (libsource (lib "eagle-import") (part "TIMS_DIODE_ZENER-DIODESOT23"))
    )
  )
  (nets
    (net (code "1") (name "+3.3VREF") (class "Default")
      (node (ref "3.3VREF") (pin "MP") (pinfunction "MP_MP") (pintype "passive"))
      (node (ref "C16") (pin "1") (pinfunction "1_1") (pintype "passive"))
      (node (ref "C30") (pin "1") (pinfunction "1_1") (pintype "passive"))
      (node (ref "C40") (pin "1") (pinfunction "1_1") (pintype "passive"))
      (node (ref "C43") (pin "1") (pinfunction "1_1") (pintype "passive"))
      (node (ref "C55") (pin "2") (pinfunction "2_2") (pintype "passive"))
      (node (ref "IC3") (pin "5") (pinfunction "V+_5") (pintype "power_in"))
      (node (ref "IC4") (pin "2") (pinfunction "OUT_2") (pintype "output"))
      (node (ref "R15") (pin "2") (pinfunction "2_2") (pintype "passive"))
      (node (ref "R21") (pin "2") (pinfunction "2_2") (pintype "passive"))
      (node (ref "U1") (pin "AREF") (pinfunction "AREF_AREF") (pintype "power_in"))
      (node (ref "U4") (pin "8") (pinfunction "VDD2_8") (pintype "power_in"))
    )
    (net (code "2") (name "+3.4VD") (class "Default")
      (node (ref "C4") (pin "1") (pinfunction "1_1") (pintype "passive"))
      (node (ref "C9") (pin "1") (pinfunction "1_1") (pintype "passive"))
      (node (ref "D5") (pin "C") (pinfunction "C_C") (pintype "passive"))
      (node (ref "L1") (pin "2") (pinfunction "2_2") (pintype "passive"))
      (node (ref "R25") (pin "1") (pinfunction "1_1") (pintype "passive"))
      (node (ref "R28") (pin "2") (pinfunction "2_2") (pintype "passive"))
      (node (ref "R36") (pin "1") (pinfunction "1_1") (pintype "passive"))
      (node (ref "R43") (pin "2") (pinfunction "2_2") (pintype "passive"))
      (node (ref "S1") (pin "3") (pinfunction "3_3") (pintype "passive"))
      (node (ref "S1") (pin "4") (pinfunction "4_4") (pintype "passive"))
      (node (ref "U1") (pin "VIN") (pinfunction "VIN_VIN") (pintype "power_in"))
    )
    (net (code "3") (name "+5V") (class "Default")
      (node (ref "5V") (pin "MP") (pinfunction "MP_MP") (pintype "passive"))
      (node (ref "C17") (pin "1") (pinfunction "1_1") (pintype "passive"))
      (node (ref "C2") (pin "1") (pinfunction "1_1") (pintype "passive"))
      (node (ref "C29") (pin "1") (pinfunction "1_1") (pintype "passive"))
      (node (ref "C38") (pin "1") (pinfunction "1_1") (pintype "passive"))
      (node (ref "C47") (pin "1") (pinfunction "1_1") (pintype "passive"))
      (node (ref "CON8") (pin "1") (pinfunction "K_1") (pintype "passive"))
      (node (ref "IC1") (pin "1") (pinfunction "IN_1") (pintype "input"))
      (node (ref "IC5") (pin "1") (pinfunction "VCC1_1") (pintype "input"))
      (node (ref "IC6") (pin "1") (pinfunction "IN_1") (pintype "input"))
      (node (ref "IC6") (pin "3") (pinfunction "EN_3") (pintype "input"))
      (node (ref "R23") (pin "1") (pinfunction "1_1") (pintype "passive"))
      (node (ref "R56") (pin "1") (pinfunction "1_1") (pintype "passive"))
      (node (ref "U2") (pin "2") (pinfunction "VO_2") (pintype "passive"))
      (node (ref "U2") (pin "4") (pinfunction "TAB_4") (pintype "passive"))
      (node (ref "U3") (pin "8") (pinfunction "+V_8") (pintype "input"))
    )
    (net (code "4") (name "5.2V-ISO") (class "Default")
      (node (ref "C37") (pin "1") (pinfunction "1_1") (pintype "passive"))
      (node (ref "C39") (pin "1") (pinfunction "1_1") (pintype "passive"))
      (node (ref "C45") (pin "1") (pinfunction "1_1") (pintype "passive"))
      (node (ref "TP-5.2VISO") (pin "MP") (pinfunction "MP_MP") (pintype "passive"))
      (node (ref "U4") (pin "1") (pinfunction "VDD1_1") (pintype "power_in"))
      (node (ref "VREG2") (pin "6") (pinfunction "+VOUT_6") (pintype "passive"))
    )
    (net (code "5") (name "12VDC{slash}666MA") (class "Default")
      (node (ref "C1") (pin "1") (pinfunction "1_1") (pintype "passive"))
      (node (ref "C11") (pin "+") (pinfunction "+_+") (pintype "passive"))
      (node (ref "C21") (pin "1") (pinfunction "1_1") (pintype "passive"))
      (node (ref "C31") (pin "1") (pinfunction "1_1") (pintype "passive"))
      (node (ref "C32") (pin "1") (pinfunction "1_1") (pintype "passive"))
      (node (ref "C44") (pin "1") (pinfunction "1_1") (pintype "passive"))
      (node (ref "D1") (pin "C") (pinfunction "C_C") (pintype "passive"))
      (node (ref "D4") (pin "C") (pinfunction "C_C") (pintype "passive"))
      (node (ref "D7") (pin "DRAIN") (pinfunction "CATHODE_DRAIN") (pintype "passive"))
      (node (ref "IC2") (pin "4") (pinfunction "V+_4") (pintype "power_in"))
      (node (ref "K1") (pin "V+") (pinfunction "V+_V+") (pintype "passive"))
      (node (ref "K2") (pin "V+") (pinfunction "V+_V+") (pintype "passive"))
      (node (ref "LED2") (pin "ANODE") (pinfunction "A_ANODE") (pintype "passive"))
      (node (ref "LED4") (pin "ANODE") (pinfunction "A_ANODE") (pintype "passive"))
      (node (ref "TP-12VDC") (pin "MP") (pinfunction "MP_MP") (pintype "passive"))
      (node (ref "U2") (pin "3") (pinfunction "VI_3") (pintype "input"))
      (node (ref "VREG2") (pin "1") (pinfunction "+VIN_1") (pintype "passive"))
    )
    (net (code "6") (name "12V{slash}100MA-OUTPUT") (class "Default")
      (node (ref "CON7") (pin "1") (pinfunction "K_1") (pintype "passive"))
      (node (ref "LED7") (pin "ANODE") (pinfunction "A_ANODE") (pintype "passive"))
      (node (ref "PTC1") (pin "1") (pinfunction "1_1") (pintype "passive"))
    )
    (net (code "7") (name "CHARGER-IN") (class "Default")
      (node (ref "LED1") (pin "CATHODE") (pinfunction "C_CATHODE") (pintype "passive"))
      (node (ref "OPTO1") (pin "4") (pinfunction "COL_4") (pintype "passive"))
      (node (ref "R25") (pin "2") (pinfunction "2_2") (pintype "passive"))
      (node (ref "U1") (pin "22/A8") (pinfunction "22/A8_22/A8") (pintype "bidirectional"))
    )
    (net (code "8") (name "CHASSIS-GND") (class "Default")
      (node (ref "CON2") (pin "2") (pinfunction "2_2") (pintype "passive"))
      (node (ref "H3") (pin "B2,8") (pinfunction "MOUNT_B2,8") (pintype "passive"))
    )
    (net (code "9") (name "DAC1-10V") (class "Default")
      (node (ref "CON5") (pin "2") (pinfunction "1_2") (pintype "passive"))
      (node (ref "LED5") (pin "ANODE") (pinfunction "A_ANODE") (pintype "passive"))
      (node (ref "R53") (pin "2") (pinfunction "2_2") (pintype "passive"))
    )
    (net (code "10") (name "DAC2-10V") (class "Default")
      (node (ref "CON3") (pin "2") (pinfunction "1_2") (pintype "passive"))
      (node (ref "LED6") (pin "ANODE") (pinfunction "A_ANODE") (pintype "passive"))
      (node (ref "R54") (pin "2") (pinfunction "2_2") (pintype "passive"))
    )
    (net (code "11") (name "ENABLE") (class "Default")
      (node (ref "IC1") (pin "3") (pinfunction "EN_3") (pintype "input"))
      (node (ref "R56") (pin "2") (pinfunction "2_2") (pintype "passive"))
      (node (ref "S3") (pin "3") (pinfunction "3_3") (pintype "passive"))
      (node (ref "S3") (pin "4") (pinfunction "4_4") (pintype "passive"))
    )
    (net (code "12") (name "GND") (class "Default")
      (node (ref "AGND") (pin "MP") (pinfunction "MP_MP") (pintype "passive"))
      (node (ref "C1") (pin "2") (pinfunction "2_2") (pintype "passive"))
      (node (ref "C10") (pin "2") (pinfunction "2_2") (pintype "passive"))
      (node (ref "C11") (pin "-") (pinfunction "-_-") (pintype "passive"))
      (node (ref "C12") (pin "2") (pinfunction "2_2") (pintype "passive"))
      (node (ref "C14") (pin "2") (pinfunction "2_2") (pintype "passive"))
      (node (ref "C15") (pin "2") (pinfunction "2_2") (pintype "passive"))
      (node (ref "C16") (pin "2") (pinfunction "2_2") (pintype "passive"))
      (node (ref "C17") (pin "2") (pinfunction "2_2") (pintype "passive"))
      (node (ref "C18") (pin "2") (pinfunction "2_2") (pintype "passive"))
      (node (ref "C19") (pin "2") (pinfunction "2_2") (pintype "passive"))
      (node (ref "C2") (pin "2") (pinfunction "2_2") (pintype "passive"))
      (node (ref "C20") (pin "2") (pinfunction "2_2") (pintype "passive"))
      (node (ref "C21") (pin "2") (pinfunction "2_2") (pintype "passive"))
      (node (ref "C23") (pin "2") (pinfunction "2_2") (pintype "passive"))
      (node (ref "C24") (pin "2") (pinfunction "2_2") (pintype "passive"))
      (node (ref "C25") (pin "1") (pinfunction "1_1") (pintype "passive"))
      (node (ref "C28") (pin "2") (pinfunction "2_2") (pintype "passive"))
      (node (ref "C29") (pin "2") (pinfunction "2_2") (pintype "passive"))
      (node (ref "C3") (pin "2") (pinfunction "2_2") (pintype "passive"))
      (node (ref "C30") (pin "2") (pinfunction "2_2") (pintype "passive"))
      (node (ref "C31") (pin "2") (pinfunction "2_2") (pintype "passive"))
      (node (ref "C32") (pin "2") (pinfunction "2_2") (pintype "passive"))
      (node (ref "C38") (pin "2") (pinfunction "2_2") (pintype "passive"))
      (node (ref "C4") (pin "2") (pinfunction "2_2") (pintype "passive"))
      (node (ref "C40") (pin "2") (pinfunction "2_2") (pintype "passive"))
      (node (ref "C41") (pin "1") (pinfunction "1_1") (pintype "passive"))
      (node (ref "C43") (pin "2") (pinfunction "2_2") (pintype "passive"))
      (node (ref "C44") (pin "2") (pinfunction "2_2") (pintype "passive"))
      (node (ref "C47") (pin "2") (pinfunction "2_2") (pintype "passive"))
      (node (ref "C48") (pin "2") (pinfunction "2_2") (pintype "passive"))
      (node (ref "C49") (pin "2") (pinfunction "2_2") (pintype "passive"))
      (node (ref "C5") (pin "2") (pinfunction "2_2") (pintype "passive"))
      (node (ref "C50") (pin "2") (pinfunction "2_2") (pintype "passive"))
      (node (ref "C51") (pin "1") (pinfunction "1_1") (pintype "passive"))
      (node (ref "C52") (pin "2") (pinfunction "2_2") (pintype "passive"))
      (node (ref "C55") (pin "1") (pinfunction "1_1") (pintype "passive"))
      (node (ref "C6") (pin "2") (pinfunction "2_2") (pintype "passive"))
      (node (ref "C7") (pin "2") (pinfunction "2_2") (pintype "passive"))
      (node (ref "C9") (pin "2") (pinfunction "2_2") (pintype "passive"))
      (node (ref "CON1") (pin "1") (pinfunction "1_1") (pintype "passive"))
      (node (ref "CON11") (pin "2") (pinfunction "2_2") (pintype "passive"))
      (node (ref "CON3") (pin "1") (pinfunction "1_1") (pintype "passive"))
      (node (ref "CON5") (pin "1") (pinfunction "1_1") (pintype "passive"))
      (node (ref "CON7") (pin "2") (pinfunction "K_2") (pintype "passive"))
      (node (ref "CON7") (pin "3") (pinfunction "K_3") (pintype "passive"))
      (node (ref "CON8") (pin "4") (pinfunction "K_4") (pintype "passive"))
      (node (ref "CON9") (pin "2") (pinfunction "K_2") (pintype "passive"))
      (node (ref "GND") (pin "MP") (pinfunction "MP_MP") (pintype "passive"))
      (node (ref "IC1") (pin "2") (pinfunction "GND_2") (pintype "power_in"))
      (node (ref "IC2") (pin "11") (pinfunction "V-_11") (pintype "power_in"))
      (node (ref "IC3") (pin "2") (pinfunction "V-_2") (pintype "power_in"))
      (node (ref "IC4") (pin "3") (pinfunction "GND_3") (pintype "power_in"))
      (node (ref "IC5") (pin "4") (pinfunction "GND1_4") (pintype "input"))
      (node (ref "IC6") (pin "2") (pinfunction "GND_2") (pintype "power_in"))
      (node (ref "LED8") (pin "CATHODE") (pinfunction "C_CATHODE") (pintype "passive"))
      (node (ref "LED9") (pin "CATHODE") (pinfunction "C_CATHODE") (pintype "passive"))
      (node (ref "NTC1") (pin "2") (pinfunction "2_2") (pintype "passive"))
      (node (ref "OPTO1") (pin "3") (pinfunction "EMIT_3") (pintype "passive"))
      (node (ref "OPTO2") (pin "3") (pinfunction "EMIT_3") (pintype "passive"))
      (node (ref "OPTO3") (pin "2") (pinfunction "C_2") (pintype "passive"))
      (node (ref "OPTO3") (pin "3") (pinfunction "EMIT_3") (pintype "passive"))
      (node (ref "OPTO4") (pin "2") (pinfunction "C_2") (pintype "passive"))
      (node (ref "OPTO4") (pin "3") (pinfunction "EMIT_3") (pintype "passive"))
      (node (ref "Q3") (pin "2") (pinfunction "S_2") (pintype "passive"))
      (node (ref "Q4") (pin "2") (pinfunction "S_2") (pintype "passive"))
      (node (ref "R1") (pin "2") (pinfunction "2_2") (pintype "passive"))
      (node (ref "R10") (pin "1") (pinfunction "1_1") (pintype "passive"))
      (node (ref "R11") (pin "2") (pinfunction "2_2") (pintype "passive"))
      (node (ref "R13") (pin "2") (pinfunction "2_2") (pintype "passive"))
      (node (ref "R14") (pin "1") (pinfunction "1_1") (pintype "passive"))
      (node (ref "R16") (pin "1") (pinfunction "1_1") (pintype "passive"))
      (node (ref "R18") (pin "1") (pinfunction "1_1") (pintype "passive"))
      (node (ref "R19") (pin "2") (pinfunction "2_2") (pintype "passive"))
      (node (ref "R24") (pin "1") (pinfunction "1_1") (pintype "passive"))
      (node (ref "R34") (pin "2") (pinfunction "2_2") (pintype "passive"))
      (node (ref "R35") (pin "2") (pinfunction "2_2") (pintype "passive"))
      (node (ref "R44") (pin "1") (pinfunction "1_1") (pintype "passive"))
      (node (ref "R45") (pin "2") (pinfunction "2_2") (pintype "passive"))
      (node (ref "R47") (pin "2") (pinfunction "2_2") (pintype "passive"))
      (node (ref "R66") (pin "1") (pinfunction "1_1") (pintype "passive"))
      (node (ref "R9") (pin "1") (pinfunction "1_1") (pintype "passive"))
      (node (ref "RN1") (pin "1") (pinfunction "1_1") (pintype "passive"))
      (node (ref "S3") (pin "1") (pinfunction "1_1") (pintype "passive"))
      (node (ref "S3") (pin "2") (pinfunction "2_2") (pintype "passive"))
      (node (ref "U1") (pin "AGND") (pinfunction "AGND_AGND") (pintype "power_in"))
      (node (ref "U1") (pin "GND") (pinfunction "GND_GND") (pintype "power_in"))
      (node (ref "U2") (pin "1") (pinfunction "GND_1") (pintype "passive"))
      (node (ref "U3") (pin "4") (pinfunction "-V_4") (pintype "input"))
      (node (ref "U3") (pin "5") (pinfunction "+INB_5") (pintype "input"))
      (node (ref "U4") (pin "5") (pinfunction "GND2_5") (pintype "power_in"))
      (node (ref "VREG1") (pin "16") (pinfunction "-VOUT_16") (pintype "input"))
      (node (ref "VREG2") (pin "2") (pinfunction "-VIN_2") (pintype "passive"))
    )
    (net (code "13") (name "ICHG") (class "Default")
      (node (ref "C3") (pin "1") (pinfunction "1_1") (pintype "passive"))
      (node (ref "CON8") (pin "3") (pinfunction "K_3") (pintype "passive"))
      (node (ref "ICHG") (pin "MP") (pinfunction "MP_MP") (pintype "passive"))
      (node (ref "R16") (pin "2") (pinfunction "2_2") (pintype "passive"))
      (node (ref "U1") (pin "A11") (pinfunction "A11_A11") (pintype "input"))
    )
    (net (code "14") (name "IDISCHG") (class "Default")
      (node (ref "C10") (pin "1") (pinfunction "1_1") (pintype "passive"))
      (node (ref "CON8") (pin "2") (pinfunction "K_2") (pintype "passive"))
      (node (ref "IDISCHG") (pin "MP") (pinfunction "MP_MP") (pintype "passive"))
      (node (ref "R66") (pin "2") (pinfunction "2_2") (pintype "passive"))
      (node (ref "U1") (pin "19/A5") (pinfunction "19/A5_19/A5") (pintype "bidirectional"))
    )
    (net (code "15") (name "KEYSWITCH-IN") (class "Default")
      (node (ref "LED3") (pin "CATHODE") (pinfunction "C_CATHODE") (pintype "passive"))
      (node (ref "OPTO2") (pin "4") (pinfunction "COL_4") (pintype "passive"))
      (node (ref "R36") (pin "2") (pinfunction "2_2") (pintype "passive"))
      (node (ref "U1") (pin "23/A9") (pinfunction "23/A9_23/A9") (pintype "bidirectional"))
    )
    (net (code "16") (name "LD1-G") (class "Default")
      (node (ref "LD1") (pin "AX") (pinfunction "AG_AX") (pintype "passive"))
      (node (ref "U1") (pin "16/A2") (pinfunction "16/A2_16/A2") (pintype "bidirectional"))
    )
    (net (code "17") (name "LD1-R") (class "Default")
      (node (ref "C6") (pin "1") (pinfunction "1_1") (pintype "passive"))
      (node (ref "LD1") (pin "AR") (pinfunction "AR_AR") (pintype "passive"))
      (node (ref "U1") (pin "15/A1") (pinfunction "15/A1_15/A1") (pintype "bidirectional"))
    )
    (net (code "18") (name "LIMP{slash}TBD") (class "Default")
      (node (ref "C52") (pin "1") (pinfunction "1_1") (pintype "passive"))
      (node (ref "CON9") (pin "1") (pinfunction "K_1") (pintype "passive"))
      (node (ref "PTC2") (pin "1") (pinfunction "1_1") (pintype "passive"))
      (node (ref "R58") (pin "2") (pinfunction "2_2") (pintype "passive"))
    )
    (net (code "19") (name "MICRO+3.3V") (class "Default")
      (node (ref "C25") (pin "2") (pinfunction "2_2") (pintype "passive"))
      (node (ref "CON1") (pin "2") (pinfunction "2_2") (pintype "passive"))
      (node (ref "U1") (pin "3.3V") (pinfunction "3.3V_3.3V") (pintype "power_in"))
    )
    (net (code "20") (name "NC-IRQ") (class "Default")
      (node (ref "CON1") (pin "8") (pinfunction "8_8") (pintype "passive"))
    )
    (net (code "21") (name "NON-ISOLATED-5V") (class "Default")
      (node (ref "C46") (pin "2") (pinfunction "2_2") (pintype "passive"))
      (node (ref "IC5") (pin "8") (pinfunction "VCC2_8") (pintype "input"))
      (node (ref "R23") (pin "2") (pinfunction "2_2") (pintype "passive"))
      (node (ref "R50") (pin "1") (pinfunction "1_1") (pintype "passive"))
    )
    (net (code "22") (name "Net-(C19-Pad1)") (class "Default")
      (node (ref "C19") (pin "1") (pinfunction "1_1") (pintype "passive"))
      (node (ref "R26") (pin "1") (pinfunction "1_1") (pintype "passive"))
      (node (ref "R30") (pin "2") (pinfunction "2_2") (pintype "passive"))
      (node (ref "TP2") (pin "MP") (pinfunction "MP_MP") (pintype "passive"))
    )
    (net (code "23") (name "Net-(C20-Pad1)") (class "Default")
      (node (ref "C20") (pin "1") (pinfunction "1_1") (pintype "passive"))
      (node (ref "R27") (pin "1") (pinfunction "1_1") (pintype "passive"))
      (node (ref "R31") (pin "2") (pinfunction "2_2") (pintype "passive"))
    )
    (net (code "24") (name "Net-(C51-Pad2)") (class "Default")
      (node (ref "C51") (pin "2") (pinfunction "2_2") (pintype "passive"))
      (node (ref "R52") (pin "1") (pinfunction "1_1") (pintype "passive"))
      (node (ref "R55") (pin "1") (pinfunction "1_1") (pintype "passive"))
    )
    (net (code "25") (name "Net-(CON1-Pad3)") (class "Default")
      (node (ref "CON1") (pin "3") (pinfunction "3_3") (pintype "passive"))
      (node (ref "U1") (pin "9") (pinfunction "9_9") (pintype "bidirectional"))
    )
    (net (code "26") (name "Net-(CON1-Pad4)") (class "Default")
      (node (ref "CON1") (pin "4") (pinfunction "4_4") (pintype "passive"))
      (node (ref "U1") (pin "10") (pinfunction "10_10") (pintype "bidirectional"))
    )
    (net (code "27") (name "Net-(CON1-Pad5)") (class "Default")
      (node (ref "CON1") (pin "5") (pinfunction "5_5") (pintype "passive"))
      (node (ref "U1") (pin "13") (pinfunction "13_13") (pintype "bidirectional"))
    )
    (net (code "28") (name "Net-(CON1-Pad6)") (class "Default")
      (node (ref "CON1") (pin "6") (pinfunction "6_6") (pintype "passive"))
      (node (ref "U1") (pin "11") (pinfunction "11_11") (pintype "bidirectional"))
    )
    (net (code "29") (name "Net-(CON1-Pad7)") (class "Default")
      (node (ref "CON1") (pin "7") (pinfunction "7_7") (pintype "passive"))
      (node (ref "U1") (pin "12") (pinfunction "12_12") (pintype "bidirectional"))
    )
    (net (code "30") (name "Net-(CON4B-1)") (class "Default")
      (node (ref "CON4") (pin "2") (pinfunction "1_2") (pintype "passive"))
      (node (ref "R29") (pin "2") (pinfunction "2_2") (pintype "passive"))
    )
    (net (code "31") (name "Net-(CON6B-1)") (class "Default")
      (node (ref "CON6") (pin "2") (pinfunction "1_2") (pintype "passive"))
      (node (ref "R32") (pin "2") (pinfunction "2_2") (pintype "passive"))
    )
    (net (code "32") (name "Net-(CON7D-K)") (class "Default")
      (node (ref "CON7") (pin "4") (pinfunction "K_4") (pintype "passive"))
      (node (ref "Q1") (pin "3") (pinfunction "D_3") (pintype "passive"))
    )
    (net (code "33") (name "Net-(CON9C-K)") (class "Default")
      (node (ref "CON9") (pin "3") (pinfunction "K_3") (pintype "passive"))
      (node (ref "NTC1") (pin "1") (pinfunction "1_1") (pintype "passive"))
      (node (ref "R21") (pin "1") (pinfunction "1_1") (pintype "passive"))
      (node (ref "U1") (pin "17/A3") (pinfunction "17/A3_17/A3") (pintype "bidirectional"))
      (node (ref "XTS") (pin "MP") (pinfunction "MP_MP") (pintype "passive"))
    )
    (net (code "34") (name "Net-(CON9D-K)") (class "Default")
      (node (ref "C15") (pin "1") (pinfunction "1_1") (pintype "passive"))
      (node (ref "CON9") (pin "4") (pinfunction "K_4") (pintype "passive"))
      (node (ref "PTC3") (pin "1") (pinfunction "1_1") (pintype "passive"))
      (node (ref "R60") (pin "2") (pinfunction "2_2") (pintype "passive"))
    )
    (net (code "35") (name "Net-(CON11-Pad1)") (class "Default")
      (node (ref "CON11") (pin "1") (pinfunction "1_1") (pintype "passive"))
      (node (ref "R10") (pin "2") (pinfunction "2_2") (pintype "passive"))
      (node (ref "TX1") (pin "MP") (pinfunction "MP_MP") (pintype "passive"))
      (node (ref "U1") (pin "1") (pinfunction "1_1") (pintype "bidirectional"))
    )
    (net (code "36") (name "Net-(CON11-Pad8)") (class "Default")
      (node (ref "CON11") (pin "8") (pinfunction "8_8") (pintype "passive"))
      (node (ref "R9") (pin "2") (pinfunction "2_2") (pintype "passive"))
      (node (ref "RX1") (pin "MP") (pinfunction "MP_MP") (pintype "passive"))
      (node (ref "U1") (pin "0") (pinfunction "0_0") (pintype "bidirectional"))
    )
    (net (code "37") (name "Net-(CONN10B-F)") (class "Default")
      (node (ref "CONN10") (pin "2") (pinfunction "F_2") (pintype "passive"))
      (node (ref "R48") (pin "2") (pinfunction "2_2") (pintype "passive"))
    )
    (net (code "38") (name "Net-(CONN10C-F)") (class "Default")
      (node (ref "CONN10") (pin "3") (pinfunction "F_3") (pintype "passive"))
      (node (ref "R51") (pin "2") (pinfunction "2_2") (pintype "passive"))
    )
    (net (code "39") (name "Net-(CONN10G-F)") (class "Default")
      (node (ref "CONN10") (pin "7") (pinfunction "F_7") (pintype "passive"))
      (node (ref "R49") (pin "2") (pinfunction "2_2") (pintype "passive"))
    )
    (net (code "40") (name "Net-(CONN10I-F)") (class "Default")
      (node (ref "CONN10") (pin "9") (pinfunction "F_9") (pintype "passive"))
      (node (ref "R50") (pin "2") (pinfunction "2_2") (pintype "passive"))
    )
    (net (code "41") (name "Net-(D2-PadC)") (class "Default")
      (node (ref "D2") (pin "C") (pinfunction "C_C") (pintype "passive"))
      (node (ref "PTC1") (pin "2") (pinfunction "2_2") (pintype "passive"))
    )
    (net (code "42") (name "Net-(D6-PadA)") (class "Default")
      (node (ref "D6") (pin "A") (pinfunction "A_A") (pintype "passive"))
      (node (ref "NTC2") (pin "1") (pinfunction "1_1") (pintype "passive"))
      (node (ref "R38") (pin "2") (pinfunction "2_2") (pintype "passive"))
    )
    (net (code "43") (name "Net-(D7-ANODE1)") (class "Default")
      (node (ref "D2") (pin "A") (pinfunction "A_A") (pintype "passive"))
      (node (ref "D7") (pin "GATE") (pinfunction "ANODE1_GATE") (pintype "passive"))
      (node (ref "D7") (pin "SOURCE") (pinfunction "ANODE2_SOURCE") (pintype "passive"))
      (node (ref "VREG1") (pin "14") (pinfunction "+VOUT_14") (pintype "input"))
    )
    (net (code "44") (name "Net-(F1-1A)") (class "Default")
      (node (ref "F1") (pin "P$1") (pinfunction "1A_P$1") (pintype "passive"))
      (node (ref "NTC2") (pin "2") (pinfunction "2_2") (pintype "passive"))
    )
    (net (code "45") (name "Net-(IC1-ADJ)") (class "Default")
      (node (ref "C5") (pin "1") (pinfunction "1_1") (pintype "passive"))
      (node (ref "IC1") (pin "4") (pinfunction "ADJ_4") (pintype "passive"))
      (node (ref "R46") (pin "1") (pinfunction "1_1") (pintype "passive"))
    )
    (net (code "46") (name "Net-(IC1-OUT)") (class "Default")
      (node (ref "+3.7V") (pin "MP") (pinfunction "MP_MP") (pintype "passive"))
      (node (ref "C12") (pin "1") (pinfunction "1_1") (pintype "passive"))
      (node (ref "C14") (pin "1") (pinfunction "1_1") (pintype "passive"))
      (node (ref "D5") (pin "A") (pinfunction "A_A") (pintype "passive"))
      (node (ref "IC1") (pin "5") (pinfunction "OUT_5") (pintype "output"))
      (node (ref "R46") (pin "2") (pinfunction "2_2") (pintype "passive"))
    )
    (net (code "47") (name "Net-(IC2A-+IN)") (class "Default")
      (node (ref "C23") (pin "1") (pinfunction "1_1") (pintype "passive"))
      (node (ref "IC2") (pin "3") (pinfunction "+IN_3") (pintype "input"))
      (node (ref "R30") (pin "1") (pinfunction "1_1") (pintype "passive"))
    )
    (net (code "48") (name "Net-(IC2A--IN)") (class "Default")
      (node (ref "IC2") (pin "2") (pinfunction "-IN_2") (pintype "input"))
      (node (ref "R34") (pin "1") (pinfunction "1_1") (pintype "passive"))
      (node (ref "R41") (pin "1") (pinfunction "1_1") (pintype "passive"))
    )
    (net (code "49") (name "Net-(IC2A-OUT)") (class "Default")
      (node (ref "IC2") (pin "1") (pinfunction "OUT_1") (pintype "output"))
      (node (ref "R41") (pin "2") (pinfunction "2_2") (pintype "passive"))
      (node (ref "R53") (pin "1") (pinfunction "1_1") (pintype "passive"))
    )
    (net (code "50") (name "Net-(IC2B-+IN)") (class "Default")
      (node (ref "C24") (pin "1") (pinfunction "1_1") (pintype "passive"))
      (node (ref "IC2") (pin "5") (pinfunction "+IN_5") (pintype "input"))
      (node (ref "R31") (pin "1") (pinfunction "1_1") (pintype "passive"))
    )
    (net (code "51") (name "Net-(IC2B--IN)") (class "Default")
      (node (ref "IC2") (pin "6") (pinfunction "-IN_6") (pintype "input"))
      (node (ref "R35") (pin "1") (pinfunction "1_1") (pintype "passive"))
      (node (ref "R42") (pin "1") (pinfunction "1_1") (pintype "passive"))
    )
    (net (code "52") (name "Net-(IC2B-OUT)") (class "Default")
      (node (ref "IC2") (pin "7") (pinfunction "OUT_7") (pintype "output"))
      (node (ref "R42") (pin "2") (pinfunction "2_2") (pintype "passive"))
      (node (ref "R54") (pin "1") (pinfunction "1_1") (pintype "passive"))
    )
    (net (code "53") (name "Net-(IC2C-+IN)") (class "Default")
      (node (ref "IC2") (pin "10") (pinfunction "+IN_10") (pintype "input"))
      (node (ref "IC2") (pin "12") (pinfunction "+IN_12") (pintype "input"))
      (node (ref "R24") (pin "2") (pinfunction "2_2") (pintype "passive"))
    )
    (net (code "54") (name "Net-(IC2C--IN)") (class "Default")
      (node (ref "IC2") (pin "8") (pinfunction "OUT_8") (pintype "output"))
      (node (ref "IC2") (pin "9") (pinfunction "-IN_9") (pintype "input"))
    )
    (net (code "55") (name "Net-(IC2D--IN)") (class "Default")
      (node (ref "IC2") (pin "13") (pinfunction "-IN_13") (pintype "input"))
      (node (ref "IC2") (pin "14") (pinfunction "OUT_14") (pintype "output"))
    )
    (net (code "56") (name "Net-(IC3-+IN)") (class "Default")
      (node (ref "C41") (pin "2") (pinfunction "2_2") (pintype "passive"))
      (node (ref "IC3") (pin "3") (pinfunction "+IN_3") (pintype "input"))
      (node (ref "RN1") (pin "7") (pinfunction "7_7") (pintype "passive"))
      (node (ref "RN1") (pin "8") (pinfunction "8_8") (pintype "passive"))
    )
    (net (code "57") (name "Net-(IC3--IN)") (class "Default")
      (node (ref "C42") (pin "2") (pinfunction "2_2") (pintype "passive"))
      (node (ref "IC3") (pin "4") (pinfunction "-IN_4") (pintype "input"))
      (node (ref "RN1") (pin "5") (pinfunction "5_5") (pintype "passive"))
      (node (ref "RN1") (pin "6") (pinfunction "6_6") (pintype "passive"))
    )
    (net (code "58") (name "Net-(IC4-IN)") (class "Default")
      (node (ref "C18") (pin "1") (pinfunction "1_1") (pintype "passive"))
      (node (ref "IC4") (pin "1") (pinfunction "IN_1") (pintype "input"))
      (node (ref "L1") (pin "1") (pinfunction "1_1") (pintype "passive"))
    )
    (net (code "59") (name "Net-(IC5-CANH)") (class "Default")
      (node (ref "IC5") (pin "7") (pinfunction "CANH_7") (pintype "input"))
      (node (ref "R49") (pin "1") (pinfunction "1_1") (pintype "passive"))
      (node (ref "R52") (pin "2") (pinfunction "2_2") (pintype "passive"))
    )
    (net (code "60") (name "Net-(IC5-CANL)") (class "Default")
      (node (ref "IC5") (pin "6") (pinfunction "CANL_6") (pintype "input"))
      (node (ref "R48") (pin "1") (pinfunction "1_1") (pintype "passive"))
      (node (ref "R55") (pin "2") (pinfunction "2_2") (pintype "passive"))
    )
    (net (code "61") (name "Net-(IC5-GND2)") (class "Default")
      (node (ref "C46") (pin "1") (pinfunction "1_1") (pintype "passive"))
      (node (ref "IC5") (pin "5") (pinfunction "GND2_5") (pintype "input"))
      (node (ref "R47") (pin "1") (pinfunction "1_1") (pintype "passive"))
      (node (ref "R51") (pin "1") (pinfunction "1_1") (pintype "passive"))
    )
    (net (code "62") (name "Net-(IC6-ADJ)") (class "Default")
      (node (ref "C48") (pin "1") (pinfunction "1_1") (pintype "passive"))
      (node (ref "IC6") (pin "4") (pinfunction "ADJ_4") (pintype "passive"))
    )
    (net (code "63") (name "Net-(IC6-OUT)") (class "Default")
      (node (ref "C49") (pin "1") (pinfunction "1_1") (pintype "passive"))
      (node (ref "C50") (pin "1") (pinfunction "1_1") (pintype "passive"))
      (node (ref "CON11") (pin "7") (pinfunction "7_7") (pintype "passive"))
      (node (ref "IC6") (pin "5") (pinfunction "OUT_5") (pintype "output"))
    )
    (net (code "64") (name "Net-(K1-PadNO)") (class "Default")
      (node (ref "K1") (pin "NO") (pinfunction "NO_NO") (pintype "passive"))
      (node (ref "TB1") (pin "3") (pinfunction "3_3") (pintype "passive"))
    )
    (net (code "65") (name "Net-(K2-PadNO)") (class "Default")
      (node (ref "K2") (pin "NO") (pinfunction "NO_NO") (pintype "passive"))
      (node (ref "TB2") (pin "3") (pinfunction "3_3") (pintype "passive"))
    )
    (net (code "66") (name "Net-(L/TBD-PadMP)") (class "Default")
      (node (ref "L/TBD") (pin "MP") (pinfunction "MP_MP") (pintype "passive"))
      (node (ref "R57") (pin "2") (pinfunction "2_2") (pintype "passive"))
      (node (ref "U1") (pin "18/A4") (pinfunction "18/A4_18/A4") (pintype "bidirectional"))
    )
    (net (code "67") (name "Net-(LD1-PadC)") (class "Default")
      (node (ref "LD1") (pin "C") (pinfunction "C_C") (pintype "passive"))
      (node (ref "R11") (pin "1") (pinfunction "1_1") (pintype "passive"))
    )
    (net (code "68") (name "Net-(LD2-AG)") (class "Default")
      (node (ref "LD2") (pin "AX") (pinfunction "AG_AX") (pintype "passive"))
      (node (ref "U1") (pin "8") (pinfunction "8_8") (pintype "bidirectional"))
    )
    (net (code "69") (name "Net-(LD2-PadAR)") (class "Default")
      (node (ref "LD2") (pin "AR") (pinfunction "AR_AR") (pintype "passive"))
      (node (ref "U1") (pin "7") (pinfunction "7_7") (pintype "bidirectional"))
    )
    (net (code "70") (name "Net-(LD2-PadC)") (class "Default")
      (node (ref "LD2") (pin "C") (pinfunction "C_C") (pintype "passive"))
      (node (ref "R13") (pin "1") (pinfunction "1_1") (pintype "passive"))
    )
    (net (code "71") (name "Net-(LED1-A)") (class "Default")
      (node (ref "LED1") (pin "ANODE") (pinfunction "A_ANODE") (pintype "passive"))
      (node (ref "R28") (pin "1") (pinfunction "1_1") (pintype "passive"))
    )
    (net (code "72") (name "Net-(LED2-C)") (class "Default")
      (node (ref "LED2") (pin "CATHODE") (pinfunction "C_CATHODE") (pintype "passive"))
      (node (ref "R6") (pin "1") (pinfunction "1_1") (pintype "passive"))
    )
    (net (code "73") (name "Net-(LED3-A)") (class "Default")
      (node (ref "LED3") (pin "ANODE") (pinfunction "A_ANODE") (pintype "passive"))
      (node (ref "R43") (pin "1") (pinfunction "1_1") (pintype "passive"))
    )
    (net (code "74") (name "Net-(LED4-C)") (class "Default")
      (node (ref "LED4") (pin "CATHODE") (pinfunction "C_CATHODE") (pintype "passive"))
      (node (ref "R8") (pin "1") (pinfunction "1_1") (pintype "passive"))
    )
    (net (code "75") (name "Net-(LED5-C)") (class "Default")
      (node (ref "LED5") (pin "CATHODE") (pinfunction "C_CATHODE") (pintype "passive"))
      (node (ref "R44") (pin "2") (pinfunction "2_2") (pintype "passive"))
    )
    (net (code "76") (name "Net-(LED6-C)") (class "Default")
      (node (ref "LED6") (pin "CATHODE") (pinfunction "C_CATHODE") (pintype "passive"))
      (node (ref "R45") (pin "1") (pinfunction "1_1") (pintype "passive"))
    )
    (net (code "77") (name "Net-(LED7-C)") (class "Default")
      (node (ref "LED7") (pin "CATHODE") (pinfunction "C_CATHODE") (pintype "passive"))
      (node (ref "R19") (pin "1") (pinfunction "1_1") (pintype "passive"))
    )
    (net (code "78") (name "Net-(LED8-A)") (class "Default")
      (node (ref "LED8") (pin "ANODE") (pinfunction "A_ANODE") (pintype "passive"))
      (node (ref "R58") (pin "1") (pinfunction "1_1") (pintype "passive"))
    )
    (net (code "79") (name "Net-(LED9-A)") (class "Default")
      (node (ref "LED9") (pin "ANODE") (pinfunction "A_ANODE") (pintype "passive"))
      (node (ref "R60") (pin "1") (pinfunction "1_1") (pintype "passive"))
    )
    (net (code "80") (name "Net-(OPTO1-A)") (class "Default")
      (node (ref "C36") (pin "1") (pinfunction "1_1") (pintype "passive"))
      (node (ref "OPTO1") (pin "1") (pinfunction "A_1") (pintype "passive"))
      (node (ref "R20") (pin "1") (pinfunction "1_1") (pintype "passive"))
    )
    (net (code "81") (name "Net-(OPTO1-C)") (class "Default")
      (node (ref "C36") (pin "2") (pinfunction "2_2") (pintype "passive"))
      (node (ref "CON4") (pin "1") (pinfunction "1_1") (pintype "passive"))
      (node (ref "OPTO1") (pin "2") (pinfunction "C_2") (pintype "passive"))
      (node (ref "R17") (pin "1") (pinfunction "1_1") (pintype "passive"))
      (node (ref "Z2") (pin "1") (pinfunction "A_1") (pintype "passive"))
    )
    (net (code "82") (name "Net-(OPTO2-A)") (class "Default")
      (node (ref "C35") (pin "1") (pinfunction "1_1") (pintype "passive"))
      (node (ref "OPTO2") (pin "1") (pinfunction "A_1") (pintype "passive"))
      (node (ref "R33") (pin "1") (pinfunction "1_1") (pintype "passive"))
    )
    (net (code "83") (name "Net-(OPTO2-C)") (class "Default")
      (node (ref "C35") (pin "2") (pinfunction "2_2") (pintype "passive"))
      (node (ref "CON6") (pin "1") (pinfunction "1_1") (pintype "passive"))
      (node (ref "OPTO2") (pin "2") (pinfunction "C_2") (pintype "passive"))
      (node (ref "R37") (pin "1") (pinfunction "1_1") (pintype "passive"))
      (node (ref "Z3") (pin "1") (pinfunction "A_1") (pintype "passive"))
    )
    (net (code "84") (name "Net-(OPTO3-A)") (class "Default")
      (node (ref "OPTO3") (pin "1") (pinfunction "A_1") (pintype "passive"))
      (node (ref "R57") (pin "1") (pinfunction "1_1") (pintype "passive"))
    )
    (net (code "85") (name "Net-(OPTO3-COL)") (class "Default")
      (node (ref "OPTO3") (pin "4") (pinfunction "COL_4") (pintype "passive"))
      (node (ref "PTC2") (pin "2") (pinfunction "2_2") (pintype "passive"))
    )
    (net (code "86") (name "Net-(OPTO4-A)") (class "Default")
      (node (ref "OPTO4") (pin "1") (pinfunction "A_1") (pintype "passive"))
      (node (ref "R59") (pin "1") (pinfunction "1_1") (pintype "passive"))
    )
    (net (code "87") (name "Net-(OPTO4-COL)") (class "Default")
      (node (ref "OPTO4") (pin "4") (pinfunction "COL_4") (pintype "passive"))
      (node (ref "PTC3") (pin "2") (pinfunction "2_2") (pintype "passive"))
    )
    (net (code "88") (name "Net-(Q1-G)") (class "Default")
      (node (ref "Q1") (pin "1") (pinfunction "G_1") (pintype "passive"))
      (node (ref "R7") (pin "1") (pinfunction "1_1") (pintype "passive"))
    )
    (net (code "89") (name "Net-(Q1-S)") (class "Default")
      (node (ref "Q1") (pin "2") (pinfunction "S_2") (pintype "passive"))
      (node (ref "R1") (pin "1") (pinfunction "1_1") (pintype "passive"))
      (node (ref "R5") (pin "2") (pinfunction "2_2") (pintype "passive"))
    )
    (net (code "90") (name "Net-(Q3-D)") (class "Default")
      (node (ref "D1") (pin "A") (pinfunction "A_A") (pintype "passive"))
      (node (ref "K1") (pin "V-") (pinfunction "V-_V-") (pintype "passive"))
      (node (ref "Q3") (pin "3") (pinfunction "D_3") (pintype "passive"))
      (node (ref "R6") (pin "2") (pinfunction "2_2") (pintype "passive"))
    )
    (net (code "91") (name "Net-(Q3-G)") (class "Default")
      (node (ref "Q3") (pin "1") (pinfunction "G_1") (pintype "passive"))
      (node (ref "R3") (pin "1") (pinfunction "1_1") (pintype "passive"))
    )
    (net (code "92") (name "Net-(Q4-D)") (class "Default")
      (node (ref "D4") (pin "A") (pinfunction "A_A") (pintype "passive"))
      (node (ref "K2") (pin "V-") (pinfunction "V-_V-") (pintype "passive"))
      (node (ref "Q4") (pin "3") (pinfunction "D_3") (pintype "passive"))
      (node (ref "R8") (pin "2") (pinfunction "2_2") (pintype "passive"))
    )
    (net (code "93") (name "Net-(Q4-G)") (class "Default")
      (node (ref "Q4") (pin "1") (pinfunction "G_1") (pintype "passive"))
      (node (ref "R4") (pin "1") (pinfunction "1_1") (pintype "passive"))
    )
    (net (code "94") (name "Net-(R12-Pad1)") (class "Default")
      (node (ref "R12") (pin "1") (pinfunction "1_1") (pintype "passive"))
      (node (ref "S1") (pin "1") (pinfunction "1_1") (pintype "passive"))
      (node (ref "S1") (pin "2") (pinfunction "2_2") (pintype "passive"))
    )
    (net (code "95") (name "Net-(R12-Pad2)") (class "Default")
      (node (ref "R12") (pin "2") (pinfunction "2_2") (pintype "passive"))
      (node (ref "R59") (pin "2") (pinfunction "2_2") (pintype "passive"))
      (node (ref "TP-SW/FAN") (pin "MP") (pinfunction "MP_MP") (pintype "passive"))
      (node (ref "U1") (pin "2") (pinfunction "2_2") (pintype "bidirectional"))
    )
    (net (code "96") (name "Net-(R14-Pad2)") (class "Default")
      (node (ref "R14") (pin "2") (pinfunction "2_2") (pintype "passive"))
      (node (ref "R15") (pin "1") (pinfunction "1_1") (pintype "passive"))
      (node (ref "U1") (pin "A10") (pinfunction "A10_A10") (pintype "input"))
      (node (ref "VBAL/2") (pin "MP") (pinfunction "MP_MP") (pintype "passive"))
    )
    (net (code "97") (name "Net-(R38-Pad1)") (class "Default")
      (node (ref "R38") (pin "1") (pinfunction "1_1") (pintype "passive"))
      (node (ref "R39") (pin "2") (pinfunction "2_2") (pintype "passive"))
    )
    (net (code "98") (name "Net-(R39-Pad1)") (class "Default")
      (node (ref "R39") (pin "1") (pinfunction "1_1") (pintype "passive"))
      (node (ref "R40") (pin "2") (pinfunction "2_2") (pintype "passive"))
    )
    (net (code "99") (name "Net-(TB1A-3)") (class "Default")
      (node (ref "K1") (pin "COM") (pinfunction "COM_COM") (pintype "passive"))
      (node (ref "TB1") (pin "1") (pinfunction "3_1") (pintype "passive"))
    )
    (net (code "100") (name "Net-(TB1B-3)") (class "Default")
      (node (ref "K1") (pin "NC") (pinfunction "NC_NC") (pintype "passive"))
      (node (ref "TB1") (pin "2") (pinfunction "3_2") (pintype "passive"))
    )
    (net (code "101") (name "Net-(TB2A-3)") (class "Default")
      (node (ref "K2") (pin "COM") (pinfunction "COM_COM") (pintype "passive"))
      (node (ref "TB2") (pin "1") (pinfunction "3_1") (pintype "passive"))
    )
    (net (code "102") (name "Net-(TB2B-3)") (class "Default")
      (node (ref "K2") (pin "NC") (pinfunction "NC_NC") (pintype "passive"))
      (node (ref "TB2") (pin "2") (pinfunction "3_2") (pintype "passive"))
    )
    (net (code "103") (name "Net-(U1-DAC)") (class "Default")
      (node (ref "R22") (pin "2") (pinfunction "2_2") (pintype "passive"))
      (node (ref "U1") (pin "14") (pinfunction "DAC_14") (pintype "output"))
    )
    (net (code "104") (name "Net-(U3-+INA)") (class "Default")
      (node (ref "C28") (pin "1") (pinfunction "1_1") (pintype "passive"))
      (node (ref "R18") (pin "2") (pinfunction "2_2") (pintype "passive"))
      (node (ref "R22") (pin "1") (pinfunction "1_1") (pintype "passive"))
      (node (ref "U3") (pin "3") (pinfunction "+INA_3") (pintype "input"))
    )
    (net (code "105") (name "Net-(U3--INA)") (class "Default")
      (node (ref "C33") (pin "2") (pinfunction "2_2") (pintype "passive"))
      (node (ref "R5") (pin "1") (pinfunction "1_1") (pintype "passive"))
      (node (ref "U3") (pin "2") (pinfunction "-INA_2") (pintype "input"))
    )
    (net (code "106") (name "Net-(U3--INB)") (class "Default")
      (node (ref "U3") (pin "6") (pinfunction "-INB_6") (pintype "input"))
      (node (ref "U3") (pin "7") (pinfunction "OUTB_7") (pintype "output"))
    )
    (net (code "107") (name "Net-(U3-OUTA)") (class "Default")
      (node (ref "C33") (pin "1") (pinfunction "1_1") (pintype "passive"))
      (node (ref "R7") (pin "2") (pinfunction "2_2") (pintype "passive"))
      (node (ref "U3") (pin "1") (pinfunction "OUTA_1") (pintype "output"))
    )
    (net (code "108") (name "Net-(U4-VIN+)") (class "Default")
      (node (ref "C8") (pin "1") (pinfunction "1_1") (pintype "passive"))
      (node (ref "R2") (pin "2") (pinfunction "2_2") (pintype "passive"))
      (node (ref "R40") (pin "1") (pinfunction "1_1") (pintype "passive"))
      (node (ref "U4") (pin "2") (pinfunction "VIN+_2") (pintype "input"))
    )
    (net (code "109") (name "Net-(U4-VOUT+)") (class "Default")
      (node (ref "RN1") (pin "2") (pinfunction "2_2") (pintype "passive"))
      (node (ref "U4") (pin "7") (pinfunction "VOUT+_7") (pintype "output"))
    )
    (net (code "110") (name "Net-(U4-VOUT-)") (class "Default")
      (node (ref "RN1") (pin "3") (pinfunction "3_3") (pintype "passive"))
      (node (ref "U4") (pin "6") (pinfunction "VOUT-_6") (pintype "output"))
    )
    (net (code "111") (name "Net-(VREG1-+VIN)") (class "Default")
      (node (ref "C13") (pin "+") (pinfunction "+_+") (pintype "passive"))
      (node (ref "C22") (pin "1") (pinfunction "1_1") (pintype "passive"))
      (node (ref "C26") (pin "1") (pinfunction "1_1") (pintype "passive"))
      (node (ref "C27") (pin "1") (pinfunction "1_1") (pintype "passive"))
      (node (ref "C34") (pin "+") (pinfunction "+_+") (pintype "passive"))
      (node (ref "D6") (pin "C") (pinfunction "C_C") (pintype "passive"))
      (node (ref "VREG1") (pin "22") (pinfunction "+VIN._22") (pintype "input"))
      (node (ref "VREG1") (pin "23") (pinfunction "+VIN_23") (pintype "input"))
      (node (ref "Z1") (pin "C") (pinfunction "C_C") (pintype "passive"))
    )
    (net (code "112") (name "Net-(VREG1-ON{slash}OFF)") (class "Default")
      (node (ref "TP-EN1") (pin "MP") (pinfunction "MP_MP") (pintype "passive"))
      (node (ref "VREG1") (pin "1") (pinfunction "ON/OFF_1") (pintype "input"))
    )
    (net (code "113") (name "Net-(Z2-C)") (class "Default")
      (node (ref "R17") (pin "2") (pinfunction "2_2") (pintype "passive"))
      (node (ref "R20") (pin "2") (pinfunction "2_2") (pintype "passive"))
      (node (ref "R29") (pin "1") (pinfunction "1_1") (pintype "passive"))
      (node (ref "Z2") (pin "3") (pinfunction "C_3") (pintype "passive"))
    )
    (net (code "114") (name "Net-(Z3-C)") (class "Default")
      (node (ref "R32") (pin "1") (pinfunction "1_1") (pintype "passive"))
      (node (ref "R33") (pin "2") (pinfunction "2_2") (pintype "passive"))
      (node (ref "R37") (pin "2") (pinfunction "2_2") (pintype "passive"))
      (node (ref "Z3") (pin "3") (pinfunction "C_3") (pintype "passive"))
    )
    (net (code "115") (name "PACKGND") (class "Default")
      (node (ref "C13") (pin "-") (pinfunction "-_-") (pintype "passive"))
      (node (ref "C22") (pin "2") (pinfunction "2_2") (pintype "passive"))
      (node (ref "C26") (pin "2") (pinfunction "2_2") (pintype "passive"))
      (node (ref "C27") (pin "2") (pinfunction "2_2") (pintype "passive"))
      (node (ref "C34") (pin "-") (pinfunction "-_-") (pintype "passive"))
      (node (ref "C37") (pin "2") (pinfunction "2_2") (pintype "passive"))
      (node (ref "C39") (pin "2") (pinfunction "2_2") (pintype "passive"))
      (node (ref "C45") (pin "2") (pinfunction "2_2") (pintype "passive"))
      (node (ref "C8") (pin "2") (pinfunction "2_2") (pintype "passive"))
      (node (ref "CON2") (pin "3") (pinfunction "3_3") (pintype "passive"))
      (node (ref "R2") (pin "1") (pinfunction "1_1") (pintype "passive"))
      (node (ref "U4") (pin "3") (pinfunction "SHDN_3") (pintype "input"))
      (node (ref "U4") (pin "4") (pinfunction "GND1_4") (pintype "power_in"))
      (node (ref "VREG1") (pin "2") (pinfunction "-VIN_2") (pintype "input"))
      (node (ref "VREG1") (pin "3") (pinfunction "-VIN._3") (pintype "input"))
      (node (ref "VREG2") (pin "4") (pinfunction "-VOUT_4") (pintype "passive"))
      (node (ref "Z1") (pin "A") (pinfunction "A_A") (pintype "passive"))
    )
    (net (code "116") (name "PWM1") (class "Default")
      (node (ref "R26") (pin "2") (pinfunction "2_2") (pintype "passive"))
      (node (ref "TP1") (pin "MP") (pinfunction "MP_MP") (pintype "passive"))
      (node (ref "U1") (pin "20/A6") (pinfunction "20/A6_20/A6") (pintype "bidirectional"))
    )
    (net (code "117") (name "PWM2") (class "Default")
      (node (ref "R27") (pin "2") (pinfunction "2_2") (pintype "passive"))
      (node (ref "TP3") (pin "MP") (pinfunction "MP_MP") (pintype "passive"))
      (node (ref "U1") (pin "21/A7") (pinfunction "21/A7_21/A7") (pintype "bidirectional"))
    )
    (net (code "118") (name "RELAYDR1") (class "Default")
      (node (ref "R3") (pin "2") (pinfunction "2_2") (pintype "passive"))
      (node (ref "TP-REL1") (pin "MP") (pinfunction "MP_MP") (pintype "passive"))
      (node (ref "U1") (pin "5") (pinfunction "5_5") (pintype "bidirectional"))
    )
    (net (code "119") (name "RELAYDR2") (class "Default")
      (node (ref "R4") (pin "2") (pinfunction "2_2") (pintype "passive"))
      (node (ref "U1") (pin "6") (pinfunction "6_6") (pintype "bidirectional"))
    )
    (net (code "120") (name "RX-CAN") (class "Default")
      (node (ref "IC5") (pin "2") (pinfunction "RXD_2") (pintype "input"))
      (node (ref "U1") (pin "4") (pinfunction "4_4") (pintype "bidirectional"))
    )
    (net (code "121") (name "TX-CAN") (class "Default")
      (node (ref "IC5") (pin "3") (pinfunction "TXD_3") (pintype "input"))
      (node (ref "U1") (pin "3") (pinfunction "3_3") (pintype "bidirectional"))
    )
    (net (code "122") (name "VPACK") (class "Default")
      (node (ref "CON2") (pin "1") (pinfunction "1_1") (pintype "passive"))
      (node (ref "F1") (pin "P$2") (pinfunction "2A_P$2") (pintype "passive"))
    )
    (net (code "123") (name "VSCALED-PACK") (class "Default")
      (node (ref "C42") (pin "1") (pinfunction "1_1") (pintype "passive"))
      (node (ref "C7") (pin "1") (pinfunction "1_1") (pintype "passive"))
      (node (ref "IC3") (pin "1") (pinfunction "OUT_1") (pintype "output"))
      (node (ref "RN1") (pin "4") (pinfunction "4_4") (pintype "passive"))
      (node (ref "U1") (pin "14/A0") (pinfunction "14/A0_14/A0") (pintype "bidirectional"))
    )
    (net (code "124") (name "unconnected-(CON11-Pad3)") (class "Default")
      (node (ref "CON11") (pin "3") (pinfunction "3_3") (pintype "passive"))
    )
    (net (code "125") (name "unconnected-(CON11-Pad4)") (class "Default")
      (node (ref "CON11") (pin "4") (pinfunction "4_4") (pintype "passive"))
    )
    (net (code "126") (name "unconnected-(CON11-Pad5)") (class "Default")
      (node (ref "CON11") (pin "5") (pinfunction "5_5") (pintype "passive"))
    )
    (net (code "127") (name "unconnected-(CON11-Pad6)") (class "Default")
      (node (ref "CON11") (pin "6") (pinfunction "6_6") (pintype "passive"))
    )
    (net (code "128") (name "unconnected-(CONN10A-F-Pad1)") (class "Default")
      (node (ref "CONN10") (pin "1") (pinfunction "F_1") (pintype "passive"))
    )
    (net (code "129") (name "unconnected-(CONN10D-F-Pad4)") (class "Default")
      (node (ref "CONN10") (pin "4") (pinfunction "F_4") (pintype "passive"))
    )
    (net (code "130") (name "unconnected-(CONN10E-F-Pad5)") (class "Default")
      (node (ref "CONN10") (pin "5") (pinfunction "F_5") (pintype "passive"))
    )
    (net (code "131") (name "unconnected-(CONN10F-F-Pad6)") (class "Default")
      (node (ref "CONN10") (pin "6") (pinfunction "F_6") (pintype "passive"))
    )
    (net (code "132") (name "unconnected-(CONN10H-F-Pad8)") (class "Default")
      (node (ref "CONN10") (pin "8") (pinfunction "F_8") (pintype "passive"))
    )
    (net (code "133") (name "unconnected-(FID1-PadTP)") (class "Default")
      (node (ref "FID1") (pin "TP") (pinfunction "TP_TP") (pintype "input"))
    )
    (net (code "134") (name "unconnected-(FID2-PadTP)") (class "Default")
      (node (ref "FID2") (pin "TP") (pinfunction "TP_TP") (pintype "input"))
    )
    (net (code "135") (name "unconnected-(FID3-PadTP)") (class "Default")
      (node (ref "FID3") (pin "TP") (pinfunction "TP_TP") (pintype "input"))
    )
    (net (code "136") (name "unconnected-(FID4-PadTP)") (class "Default")
      (node (ref "FID4") (pin "TP") (pinfunction "TP_TP") (pintype "input"))
    )
    (net (code "137") (name "unconnected-(VREG1-NC-Pad11)") (class "Default")
      (node (ref "VREG1") (pin "11") (pinfunction "NC_11") (pintype "input"))
    )
    (net (code "138") (name "unconnected-(VREG1-NOPIN-Pad9)") (class "Default")
      (node (ref "VREG1") (pin "9") (pinfunction "NOPIN_9") (pintype "input"))
    )
  )
)
